# stereo_mix_back_digital.net
KiCad netlist of a schematic drawn in EAGLE
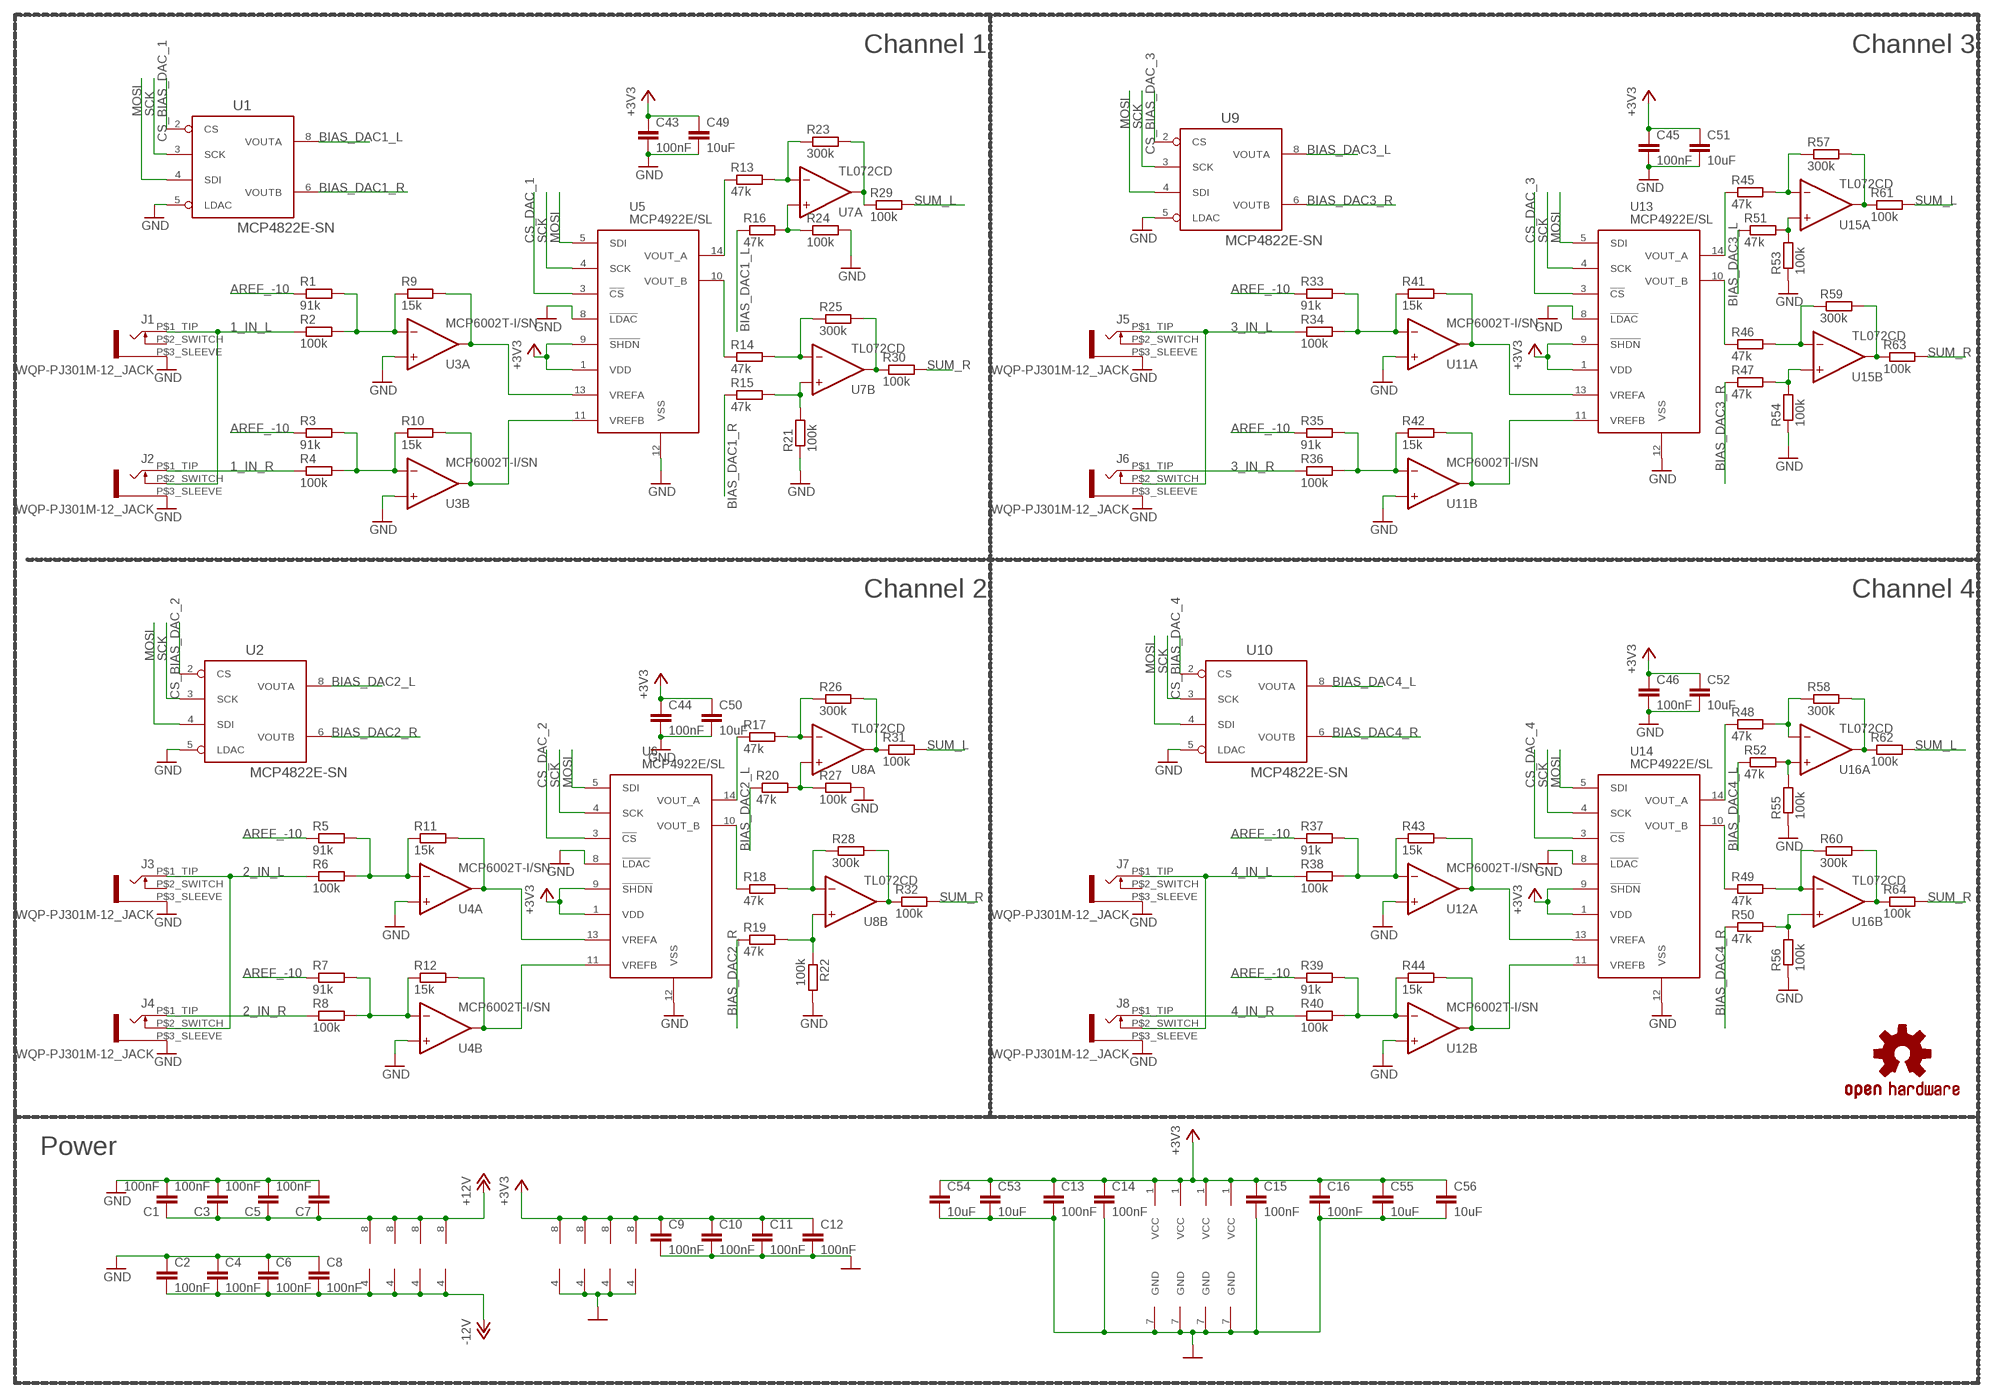
[diagram p0: schematic, sheet 1]
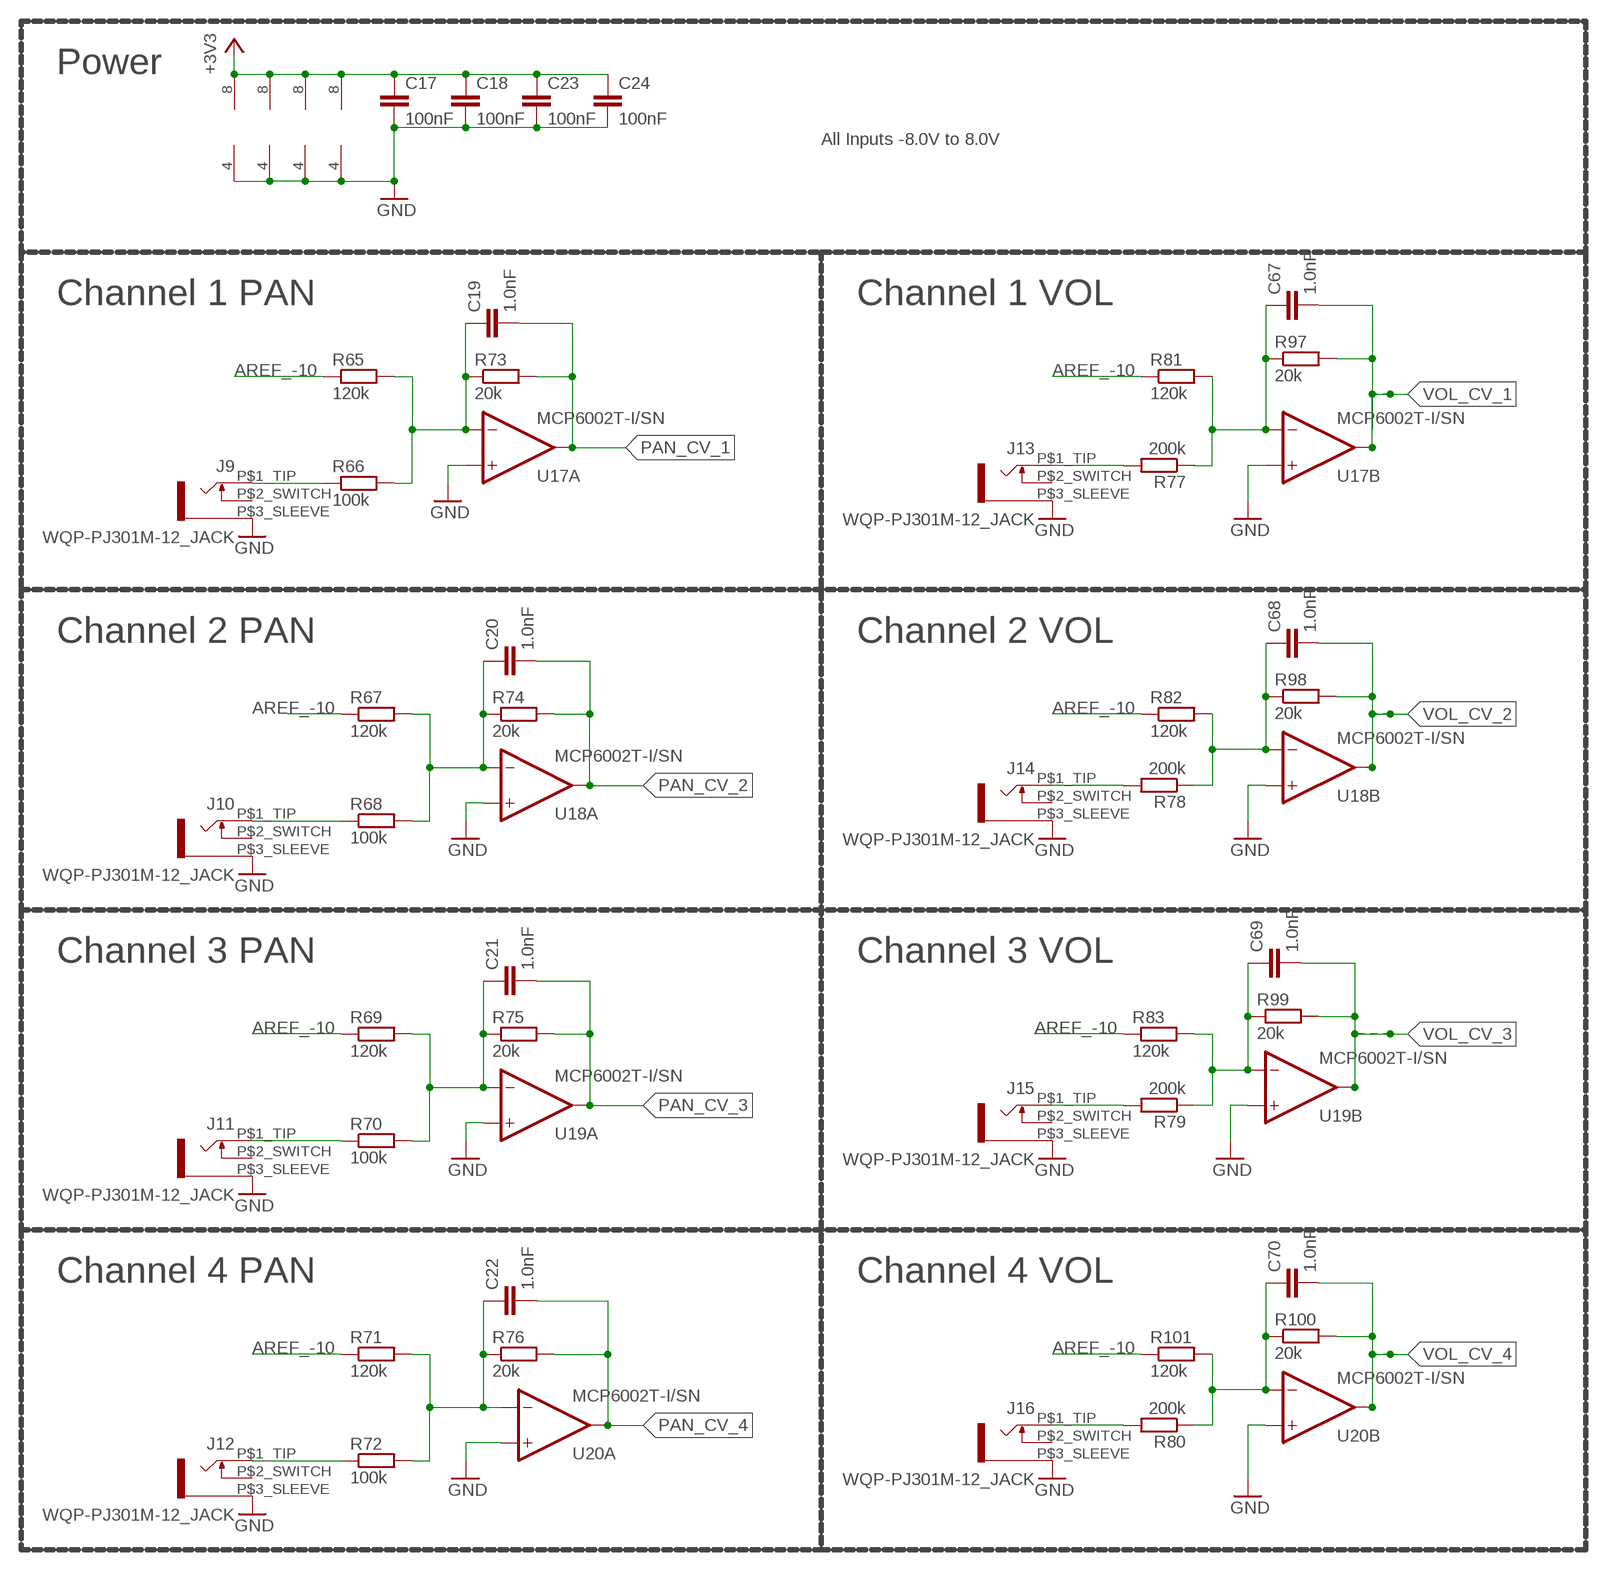
[diagram p1: schematic, sheet 2]
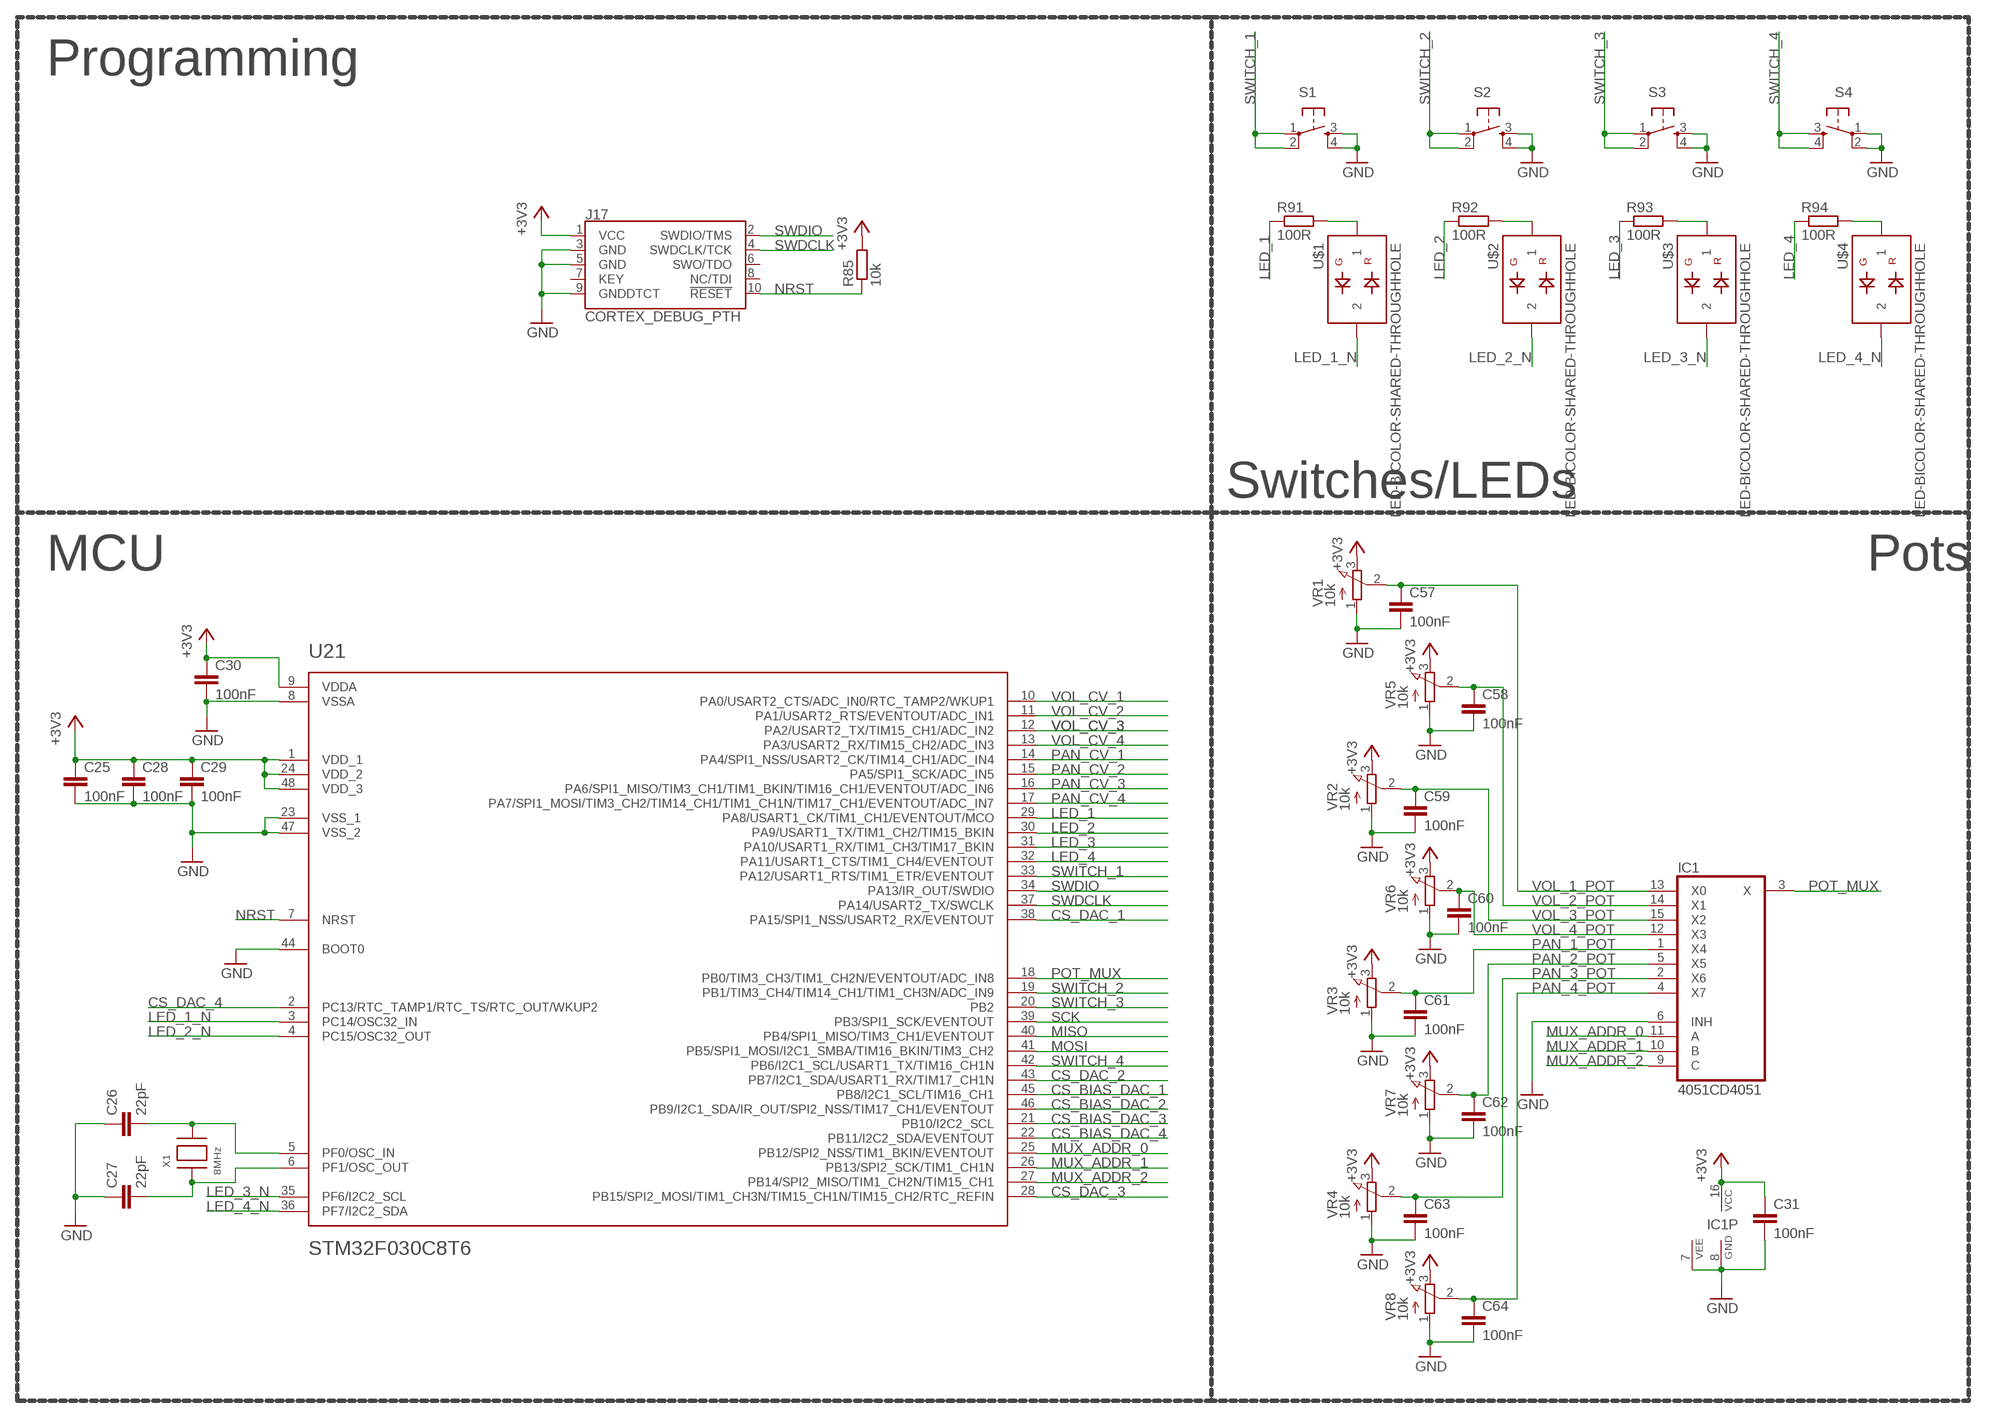
[diagram p2: schematic, sheet 3]
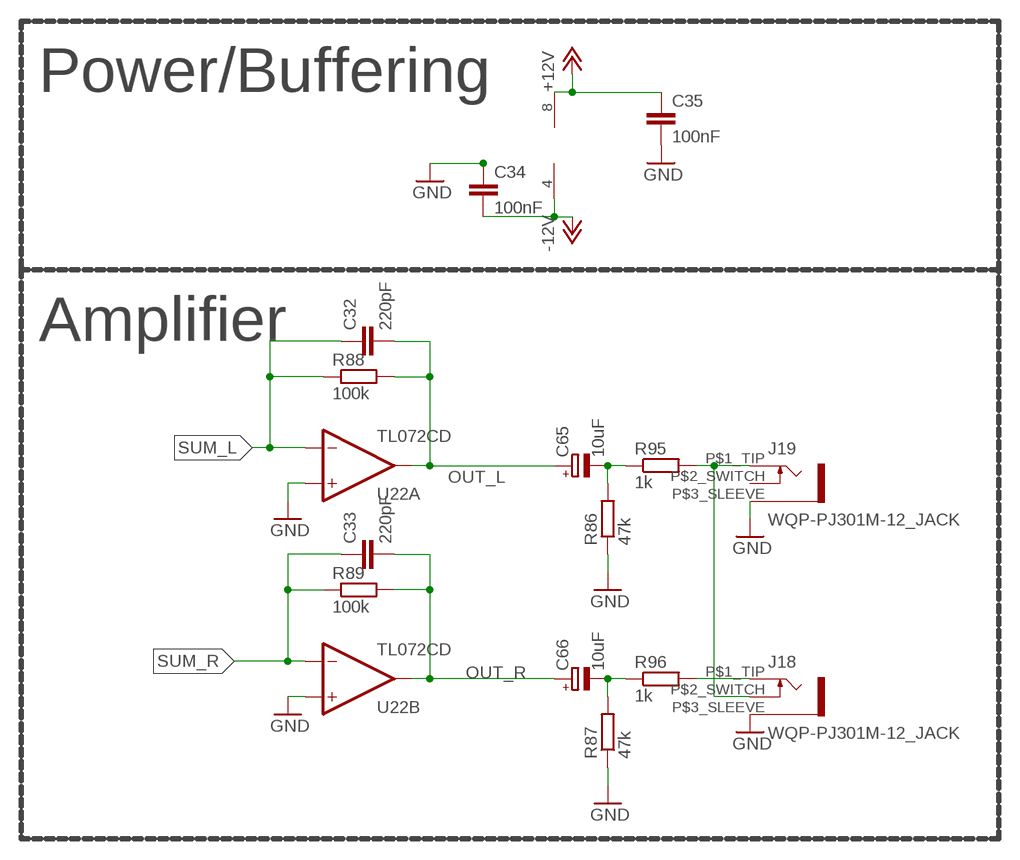
[diagram p3: schematic, sheet 4]
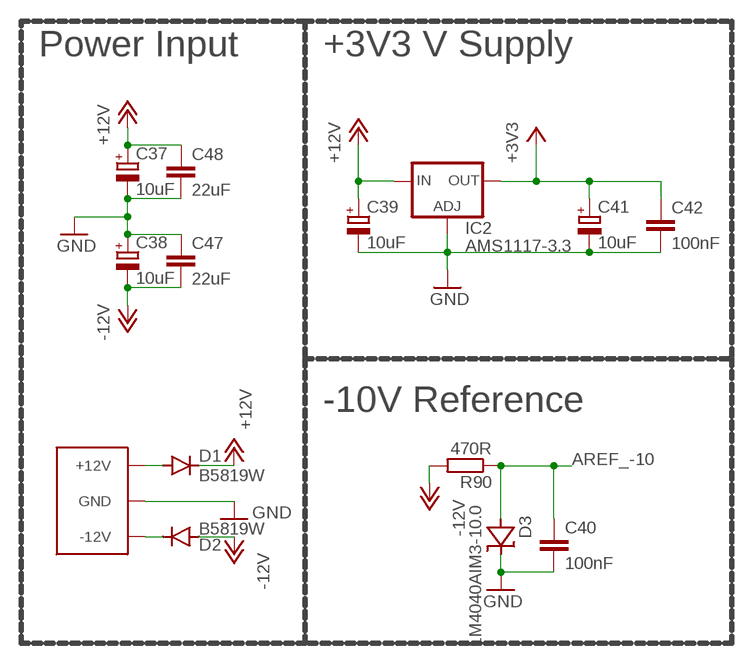
[diagram p4: schematic, sheet 5]

(export (version "E")
  (design (tool "Eeschema 10.0.6"))
  (components
    (comp (ref "C1")
      (value "100nF")
      (footprint "eagle-import:C0402")
      (libsource (lib "eagle-import") (part "C-EUC0402"))
    )
    (comp (ref "C2")
      (value "100nF")
      (footprint "eagle-import:C0402")
      (libsource (lib "eagle-import") (part "C-EUC0402"))
    )
    (comp (ref "C3")
      (value "100nF")
      (footprint "eagle-import:C0402")
      (libsource (lib "eagle-import") (part "C-EUC0402"))
    )
    (comp (ref "C4")
      (value "100nF")
      (footprint "eagle-import:C0402")
      (libsource (lib "eagle-import") (part "C-EUC0402"))
    )
    (comp (ref "C5")
      (value "100nF")
      (footprint "eagle-import:C0402")
      (libsource (lib "eagle-import") (part "C-EUC0402"))
    )
    (comp (ref "C6")
      (value "100nF")
      (footprint "eagle-import:C0402")
      (libsource (lib "eagle-import") (part "C-EUC0402"))
    )
    (comp (ref "C7")
      (value "100nF")
      (footprint "eagle-import:C0402")
      (libsource (lib "eagle-import") (part "C-EUC0402"))
    )
    (comp (ref "C8")
      (value "100nF")
      (footprint "eagle-import:C0402")
      (libsource (lib "eagle-import") (part "C-EUC0402"))
    )
    (comp (ref "C9")
      (value "100nF")
      (footprint "eagle-import:C0402")
      (libsource (lib "eagle-import") (part "C-EUC0402"))
    )
    (comp (ref "C10")
      (value "100nF")
      (footprint "eagle-import:C0402")
      (libsource (lib "eagle-import") (part "C-EUC0402"))
    )
    (comp (ref "C11")
      (value "100nF")
      (footprint "eagle-import:C0402")
      (libsource (lib "eagle-import") (part "C-EUC0402"))
    )
    (comp (ref "C12")
      (value "100nF")
      (footprint "eagle-import:C0402")
      (libsource (lib "eagle-import") (part "C-EUC0402"))
    )
    (comp (ref "C13")
      (value "100nF")
      (footprint "eagle-import:C0402")
      (libsource (lib "eagle-import") (part "C-EUC0402"))
    )
    (comp (ref "C14")
      (value "100nF")
      (footprint "eagle-import:C0402")
      (libsource (lib "eagle-import") (part "C-EUC0402"))
    )
    (comp (ref "C15")
      (value "100nF")
      (footprint "eagle-import:C0402")
      (libsource (lib "eagle-import") (part "C-EUC0402"))
    )
    (comp (ref "C16")
      (value "100nF")
      (footprint "eagle-import:C0402")
      (libsource (lib "eagle-import") (part "C-EUC0402"))
    )
    (comp (ref "C43")
      (value "100nF")
      (footprint "eagle-import:C0402")
      (libsource (lib "eagle-import") (part "C-EUC0402"))
    )
    (comp (ref "C44")
      (value "100nF")
      (footprint "eagle-import:C0402")
      (libsource (lib "eagle-import") (part "C-EUC0402"))
    )
    (comp (ref "C45")
      (value "100nF")
      (footprint "eagle-import:C0402")
      (libsource (lib "eagle-import") (part "jhbruhn-cr_C-EUC0402"))
    )
    (comp (ref "C46")
      (value "100nF")
      (footprint "eagle-import:C0402")
      (libsource (lib "eagle-import") (part "jhbruhn-cr_C-EUC0402"))
    )
    (comp (ref "C49")
      (value "10uF")
      (footprint "eagle-import:C0805")
      (libsource (lib "eagle-import") (part "C-EUC0805"))
    )
    (comp (ref "C50")
      (value "10uF")
      (footprint "eagle-import:C0805")
      (libsource (lib "eagle-import") (part "C-EUC0805"))
    )
    (comp (ref "C51")
      (value "10uF")
      (footprint "eagle-import:C0805")
      (libsource (lib "eagle-import") (part "C-EUC0805"))
    )
    (comp (ref "C52")
      (value "10uF")
      (footprint "eagle-import:C0805")
      (libsource (lib "eagle-import") (part "C-EUC0805"))
    )
    (comp (ref "C53")
      (value "10uF")
      (footprint "eagle-import:C0805")
      (libsource (lib "eagle-import") (part "C-EUC0805"))
    )
    (comp (ref "C54")
      (value "10uF")
      (footprint "eagle-import:C0805")
      (libsource (lib "eagle-import") (part "C-EUC0805"))
    )
    (comp (ref "C55")
      (value "10uF")
      (footprint "eagle-import:C0805")
      (libsource (lib "eagle-import") (part "C-EUC0805"))
    )
    (comp (ref "C56")
      (value "10uF")
      (footprint "eagle-import:C0805")
      (libsource (lib "eagle-import") (part "C-EUC0805"))
    )
    (comp (ref "J1")
      (value "WQP-PJ301M-12_JACK")
      (footprint "eagle-import:WQP-PJ301M-12_JACK")
      (libsource (lib "eagle-import") (part "WQP-PJ301M-12_JACK"))
    )
    (comp (ref "J2")
      (value "WQP-PJ301M-12_JACK")
      (footprint "eagle-import:WQP-PJ301M-12_JACK")
      (libsource (lib "eagle-import") (part "WQP-PJ301M-12_JACK"))
    )
    (comp (ref "J3")
      (value "WQP-PJ301M-12_JACK")
      (footprint "eagle-import:WQP-PJ301M-12_JACK")
      (libsource (lib "eagle-import") (part "WQP-PJ301M-12_JACK"))
    )
    (comp (ref "J4")
      (value "WQP-PJ301M-12_JACK")
      (footprint "eagle-import:WQP-PJ301M-12_JACK")
      (libsource (lib "eagle-import") (part "WQP-PJ301M-12_JACK"))
    )
    (comp (ref "J5")
      (value "WQP-PJ301M-12_JACK")
      (footprint "eagle-import:WQP-PJ301M-12_JACK")
      (libsource (lib "eagle-import") (part "WQP-PJ301M-12_JACK"))
    )
    (comp (ref "J6")
      (value "WQP-PJ301M-12_JACK")
      (footprint "eagle-import:WQP-PJ301M-12_JACK")
      (libsource (lib "eagle-import") (part "WQP-PJ301M-12_JACK"))
    )
    (comp (ref "J7")
      (value "WQP-PJ301M-12_JACK")
      (footprint "eagle-import:WQP-PJ301M-12_JACK")
      (libsource (lib "eagle-import") (part "WQP-PJ301M-12_JACK"))
    )
    (comp (ref "J8")
      (value "WQP-PJ301M-12_JACK")
      (footprint "eagle-import:WQP-PJ301M-12_JACK")
      (libsource (lib "eagle-import") (part "WQP-PJ301M-12_JACK"))
    )
    (comp (ref "LOGO1")
      (value "OSHW-LOGOS")
      (footprint "eagle-import:OSHW-LOGO-S")
      (libsource (lib "eagle-import") (part "OSHW-LOGOS"))
    )
    (comp (ref "R1")
      (value "91k")
      (footprint "eagle-import:R0402")
      (libsource (lib "eagle-import") (part "jhbruhn-cr_R-EU_R0402"))
    )
    (comp (ref "R2")
      (value "100k")
      (footprint "eagle-import:R0402")
      (libsource (lib "eagle-import") (part "jhbruhn-cr_R-EU_R0402"))
    )
    (comp (ref "R3")
      (value "91k")
      (footprint "eagle-import:R0402")
      (libsource (lib "eagle-import") (part "jhbruhn-cr_R-EU_R0402"))
    )
    (comp (ref "R4")
      (value "100k")
      (footprint "eagle-import:R0402")
      (libsource (lib "eagle-import") (part "jhbruhn-cr_R-EU_R0402"))
    )
    (comp (ref "R5")
      (value "91k")
      (footprint "eagle-import:R0402")
      (libsource (lib "eagle-import") (part "jhbruhn-cr_R-EU_R0402"))
    )
    (comp (ref "R6")
      (value "100k")
      (footprint "eagle-import:R0402")
      (libsource (lib "eagle-import") (part "jhbruhn-cr_R-EU_R0402"))
    )
    (comp (ref "R7")
      (value "91k")
      (footprint "eagle-import:R0402")
      (libsource (lib "eagle-import") (part "jhbruhn-cr_R-EU_R0402"))
    )
    (comp (ref "R8")
      (value "100k")
      (footprint "eagle-import:R0402")
      (libsource (lib "eagle-import") (part "jhbruhn-cr_R-EU_R0402"))
    )
    (comp (ref "R9")
      (value "15k")
      (footprint "eagle-import:R0402")
      (libsource (lib "eagle-import") (part "jhbruhn-cr_R-EU_R0402"))
    )
    (comp (ref "R10")
      (value "15k")
      (footprint "eagle-import:R0402")
      (libsource (lib "eagle-import") (part "jhbruhn-cr_R-EU_R0402"))
    )
    (comp (ref "R11")
      (value "15k")
      (footprint "eagle-import:R0402")
      (libsource (lib "eagle-import") (part "jhbruhn-cr_R-EU_R0402"))
    )
    (comp (ref "R12")
      (value "15k")
      (footprint "eagle-import:R0402")
      (libsource (lib "eagle-import") (part "jhbruhn-cr_R-EU_R0402"))
    )
    (comp (ref "R13")
      (value "47k")
      (footprint "eagle-import:R0402")
      (libsource (lib "eagle-import") (part "jhbruhn-cr_R-EU_R0402"))
    )
    (comp (ref "R14")
      (value "47k")
      (footprint "eagle-import:R0402")
      (libsource (lib "eagle-import") (part "jhbruhn-cr_R-EU_R0402"))
    )
    (comp (ref "R15")
      (value "47k")
      (footprint "eagle-import:R0402")
      (libsource (lib "eagle-import") (part "jhbruhn-cr_R-EU_R0402"))
    )
    (comp (ref "R16")
      (value "47k")
      (footprint "eagle-import:R0402")
      (libsource (lib "eagle-import") (part "jhbruhn-cr_R-EU_R0402"))
    )
    (comp (ref "R17")
      (value "47k")
      (footprint "eagle-import:R0402")
      (libsource (lib "eagle-import") (part "jhbruhn-cr_R-EU_R0402"))
    )
    (comp (ref "R18")
      (value "47k")
      (footprint "eagle-import:R0402")
      (libsource (lib "eagle-import") (part "jhbruhn-cr_R-EU_R0402"))
    )
    (comp (ref "R19")
      (value "47k")
      (footprint "eagle-import:R0402")
      (libsource (lib "eagle-import") (part "jhbruhn-cr_R-EU_R0402"))
    )
    (comp (ref "R20")
      (value "47k")
      (footprint "eagle-import:R0402")
      (libsource (lib "eagle-import") (part "jhbruhn-cr_R-EU_R0402"))
    )
    (comp (ref "R21")
      (value "100k")
      (footprint "eagle-import:R0402")
      (libsource (lib "eagle-import") (part "jhbruhn-cr_R-EU_R0402"))
    )
    (comp (ref "R22")
      (value "100k")
      (footprint "eagle-import:R0402")
      (libsource (lib "eagle-import") (part "jhbruhn-cr_R-EU_R0402"))
    )
    (comp (ref "R23")
      (value "300k")
      (footprint "eagle-import:R0402")
      (libsource (lib "eagle-import") (part "jhbruhn-cr_R-EU_R0402"))
    )
    (comp (ref "R24")
      (value "100k")
      (footprint "eagle-import:R0402")
      (libsource (lib "eagle-import") (part "jhbruhn-cr_R-EU_R0402"))
    )
    (comp (ref "R25")
      (value "300k")
      (footprint "eagle-import:R0402")
      (libsource (lib "eagle-import") (part "jhbruhn-cr_R-EU_R0402"))
    )
    (comp (ref "R26")
      (value "300k")
      (footprint "eagle-import:R0402")
      (libsource (lib "eagle-import") (part "jhbruhn-cr_R-EU_R0402"))
    )
    (comp (ref "R27")
      (value "100k")
      (footprint "eagle-import:R0402")
      (libsource (lib "eagle-import") (part "jhbruhn-cr_R-EU_R0402"))
    )
    (comp (ref "R28")
      (value "300k")
      (footprint "eagle-import:R0402")
      (libsource (lib "eagle-import") (part "jhbruhn-cr_R-EU_R0402"))
    )
    (comp (ref "R29")
      (value "100k")
      (footprint "eagle-import:R0402")
      (libsource (lib "eagle-import") (part "jhbruhn-cr_R-EU_R0402"))
    )
    (comp (ref "R30")
      (value "100k")
      (footprint "eagle-import:R0402")
      (libsource (lib "eagle-import") (part "jhbruhn-cr_R-EU_R0402"))
    )
    (comp (ref "R31")
      (value "100k")
      (footprint "eagle-import:R0402")
      (libsource (lib "eagle-import") (part "jhbruhn-cr_R-EU_R0402"))
    )
    (comp (ref "R32")
      (value "100k")
      (footprint "eagle-import:R0402")
      (libsource (lib "eagle-import") (part "jhbruhn-cr_R-EU_R0402"))
    )
    (comp (ref "R33")
      (value "91k")
      (footprint "eagle-import:R0402")
      (libsource (lib "eagle-import") (part "jhbruhn-cr_R-EU_R0402"))
    )
    (comp (ref "R34")
      (value "100k")
      (footprint "eagle-import:R0402")
      (libsource (lib "eagle-import") (part "jhbruhn-cr_R-EU_R0402"))
    )
    (comp (ref "R35")
      (value "91k")
      (footprint "eagle-import:R0402")
      (libsource (lib "eagle-import") (part "jhbruhn-cr_R-EU_R0402"))
    )
    (comp (ref "R36")
      (value "100k")
      (footprint "eagle-import:R0402")
      (libsource (lib "eagle-import") (part "jhbruhn-cr_R-EU_R0402"))
    )
    (comp (ref "R37")
      (value "91k")
      (footprint "eagle-import:R0402")
      (libsource (lib "eagle-import") (part "jhbruhn-cr_R-EU_R0402"))
    )
    (comp (ref "R38")
      (value "100k")
      (footprint "eagle-import:R0402")
      (libsource (lib "eagle-import") (part "jhbruhn-cr_R-EU_R0402"))
    )
    (comp (ref "R39")
      (value "91k")
      (footprint "eagle-import:R0402")
      (libsource (lib "eagle-import") (part "jhbruhn-cr_R-EU_R0402"))
    )
    (comp (ref "R40")
      (value "100k")
      (footprint "eagle-import:R0402")
      (libsource (lib "eagle-import") (part "jhbruhn-cr_R-EU_R0402"))
    )
    (comp (ref "R41")
      (value "15k")
      (footprint "eagle-import:R0402")
      (libsource (lib "eagle-import") (part "jhbruhn-cr_R-EU_R0402"))
    )
    (comp (ref "R42")
      (value "15k")
      (footprint "eagle-import:R0402")
      (libsource (lib "eagle-import") (part "jhbruhn-cr_R-EU_R0402"))
    )
    (comp (ref "R43")
      (value "15k")
      (footprint "eagle-import:R0402")
      (libsource (lib "eagle-import") (part "jhbruhn-cr_R-EU_R0402"))
    )
    (comp (ref "R44")
      (value "15k")
      (footprint "eagle-import:R0402")
      (libsource (lib "eagle-import") (part "jhbruhn-cr_R-EU_R0402"))
    )
    (comp (ref "R45")
      (value "47k")
      (footprint "eagle-import:R0402")
      (libsource (lib "eagle-import") (part "jhbruhn-cr_R-EU_R0402"))
    )
    (comp (ref "R46")
      (value "47k")
      (footprint "eagle-import:R0402")
      (libsource (lib "eagle-import") (part "jhbruhn-cr_R-EU_R0402"))
    )
    (comp (ref "R47")
      (value "47k")
      (footprint "eagle-import:R0402")
      (libsource (lib "eagle-import") (part "jhbruhn-cr_R-EU_R0402"))
    )
    (comp (ref "R48")
      (value "47k")
      (footprint "eagle-import:R0402")
      (libsource (lib "eagle-import") (part "jhbruhn-cr_R-EU_R0402"))
    )
    (comp (ref "R49")
      (value "47k")
      (footprint "eagle-import:R0402")
      (libsource (lib "eagle-import") (part "jhbruhn-cr_R-EU_R0402"))
    )
    (comp (ref "R50")
      (value "47k")
      (footprint "eagle-import:R0402")
      (libsource (lib "eagle-import") (part "jhbruhn-cr_R-EU_R0402"))
    )
    (comp (ref "R51")
      (value "47k")
      (footprint "eagle-import:R0402")
      (libsource (lib "eagle-import") (part "jhbruhn-cr_R-EU_R0402"))
    )
    (comp (ref "R52")
      (value "47k")
      (footprint "eagle-import:R0402")
      (libsource (lib "eagle-import") (part "jhbruhn-cr_R-EU_R0402"))
    )
    (comp (ref "R53")
      (value "100k")
      (footprint "eagle-import:R0402")
      (libsource (lib "eagle-import") (part "jhbruhn-cr_R-EU_R0402"))
    )
    (comp (ref "R54")
      (value "100k")
      (footprint "eagle-import:R0402")
      (libsource (lib "eagle-import") (part "jhbruhn-cr_R-EU_R0402"))
    )
    (comp (ref "R55")
      (value "100k")
      (footprint "eagle-import:R0402")
      (libsource (lib "eagle-import") (part "jhbruhn-cr_R-EU_R0402"))
    )
    (comp (ref "R56")
      (value "100k")
      (footprint "eagle-import:R0402")
      (libsource (lib "eagle-import") (part "jhbruhn-cr_R-EU_R0402"))
    )
    (comp (ref "R57")
      (value "300k")
      (footprint "eagle-import:R0402")
      (libsource (lib "eagle-import") (part "jhbruhn-cr_R-EU_R0402"))
    )
    (comp (ref "R58")
      (value "300k")
      (footprint "eagle-import:R0402")
      (libsource (lib "eagle-import") (part "jhbruhn-cr_R-EU_R0402"))
    )
    (comp (ref "R59")
      (value "300k")
      (footprint "eagle-import:R0402")
      (libsource (lib "eagle-import") (part "jhbruhn-cr_R-EU_R0402"))
    )
    (comp (ref "R60")
      (value "300k")
      (footprint "eagle-import:R0402")
      (libsource (lib "eagle-import") (part "jhbruhn-cr_R-EU_R0402"))
    )
    (comp (ref "R61")
      (value "100k")
      (footprint "eagle-import:R0402")
      (libsource (lib "eagle-import") (part "jhbruhn-cr_R-EU_R0402"))
    )
    (comp (ref "R62")
      (value "100k")
      (footprint "eagle-import:R0402")
      (libsource (lib "eagle-import") (part "jhbruhn-cr_R-EU_R0402"))
    )
    (comp (ref "R63")
      (value "100k")
      (footprint "eagle-import:R0402")
      (libsource (lib "eagle-import") (part "jhbruhn-cr_R-EU_R0402"))
    )
    (comp (ref "R64")
      (value "100k")
      (footprint "eagle-import:R0402")
      (libsource (lib "eagle-import") (part "jhbruhn-cr_R-EU_R0402"))
    )
    (comp (ref "U1")
      (value "MCP4822E-SN")
      (footprint "eagle-import:SOIC8")
      (libsource (lib "eagle-import") (part "MCP482E-SN2"))
    )
    (comp (ref "U2")
      (value "MCP4822E-SN")
      (footprint "eagle-import:SOIC8")
      (libsource (lib "eagle-import") (part "MCP482E-SN2"))
    )
    (comp (ref "U3")
      (value "MCP6002T-I/SN")
      (footprint "eagle-import:SOIC8")
      (libsource (lib "eagle-import") (part "MCP6002T-I/SN"))
    )
    (comp (ref "U4")
      (value "MCP6002T-I/SN")
      (footprint "eagle-import:SOIC8")
      (libsource (lib "eagle-import") (part "MCP6002T-I/SN"))
    )
    (comp (ref "U5")
      (value "MCP4922E/SL")
      (footprint "eagle-import:SO-14")
      (libsource (lib "eagle-import") (part "MCP492E/SL2"))
    )
    (comp (ref "U6")
      (value "MCP4922E/SL")
      (footprint "eagle-import:SO-14")
      (libsource (lib "eagle-import") (part "MCP492E/SL2"))
    )
    (comp (ref "U7")
      (value "TL072CD")
      (footprint "eagle-import:SOIC8")
      (libsource (lib "eagle-import") (part "TL072DC"))
    )
    (comp (ref "U8")
      (value "TL072CD")
      (footprint "eagle-import:SOIC8")
      (libsource (lib "eagle-import") (part "TL072DC"))
    )
    (comp (ref "U9")
      (value "MCP4822E-SN")
      (footprint "eagle-import:SOIC8")
      (libsource (lib "eagle-import") (part "MCP482E-SN2"))
    )
    (comp (ref "U10")
      (value "MCP4822E-SN")
      (footprint "eagle-import:SOIC8")
      (libsource (lib "eagle-import") (part "MCP482E-SN2"))
    )
    (comp (ref "U11")
      (value "MCP6002T-I/SN")
      (footprint "eagle-import:SOIC8")
      (libsource (lib "eagle-import") (part "MCP6002T-I/SN"))
    )
    (comp (ref "U12")
      (value "MCP6002T-I/SN")
      (footprint "eagle-import:SOIC8")
      (libsource (lib "eagle-import") (part "MCP6002T-I/SN"))
    )
    (comp (ref "U13")
      (value "MCP4922E/SL")
      (footprint "eagle-import:SO-14")
      (libsource (lib "eagle-import") (part "MCP492E/SL2"))
    )
    (comp (ref "U14")
      (value "MCP4922E/SL")
      (footprint "eagle-import:SO-14")
      (libsource (lib "eagle-import") (part "MCP492E/SL2"))
    )
    (comp (ref "U15")
      (value "TL072CD")
      (footprint "eagle-import:SOIC8")
      (libsource (lib "eagle-import") (part "TL072DC"))
    )
    (comp (ref "U16")
      (value "TL072CD")
      (footprint "eagle-import:SOIC8")
      (libsource (lib "eagle-import") (part "TL072DC"))
    )
    (comp (ref "C25")
      (value "100nF")
      (footprint "eagle-import:C0402")
      (libsource (lib "eagle-import") (part "C-EUC0402"))
    )
    (comp (ref "C26")
      (value "22pF")
      (footprint "eagle-import:C0402")
      (libsource (lib "eagle-import") (part "C-EUC0402"))
    )
    (comp (ref "C27")
      (value "22pF")
      (footprint "eagle-import:C0402")
      (libsource (lib "eagle-import") (part "C-EUC0402"))
    )
    (comp (ref "C28")
      (value "100nF")
      (footprint "eagle-import:C0402")
      (libsource (lib "eagle-import") (part "C-EUC0402"))
    )
    (comp (ref "C29")
      (value "100nF")
      (footprint "eagle-import:C0402")
      (libsource (lib "eagle-import") (part "C-EUC0402"))
    )
    (comp (ref "C30")
      (value "100nF")
      (footprint "eagle-import:C0402")
      (libsource (lib "eagle-import") (part "C-EUC0402"))
    )
    (comp (ref "C31")
      (value "100nF")
      (footprint "eagle-import:C0402")
      (libsource (lib "eagle-import") (part "C-EUC0402"))
    )
    (comp (ref "C57")
      (value "100nF")
      (footprint "eagle-import:C0402")
      (libsource (lib "eagle-import") (part "C-EUC0402"))
    )
    (comp (ref "C58")
      (value "100nF")
      (footprint "eagle-import:C0402")
      (libsource (lib "eagle-import") (part "C-EUC0402"))
    )
    (comp (ref "C59")
      (value "100nF")
      (footprint "eagle-import:C0402")
      (libsource (lib "eagle-import") (part "C-EUC0402"))
    )
    (comp (ref "C60")
      (value "100nF")
      (footprint "eagle-import:C0402")
      (libsource (lib "eagle-import") (part "C-EUC0402"))
    )
    (comp (ref "C61")
      (value "100nF")
      (footprint "eagle-import:C0402")
      (libsource (lib "eagle-import") (part "C-EUC0402"))
    )
    (comp (ref "C62")
      (value "100nF")
      (footprint "eagle-import:C0402")
      (libsource (lib "eagle-import") (part "C-EUC0402"))
    )
    (comp (ref "C63")
      (value "100nF")
      (footprint "eagle-import:C0402")
      (libsource (lib "eagle-import") (part "C-EUC0402"))
    )
    (comp (ref "C64")
      (value "100nF")
      (footprint "eagle-import:C0402")
      (libsource (lib "eagle-import") (part "C-EUC0402"))
    )
    (comp (ref "IC1")
      (value "4051CD4051")
      (footprint "eagle-import:SOIC16N")
      (libsource (lib "eagle-import") (part "4051CD4051"))
    )
    (comp (ref "J17")
      (value "CORTEX_DEBUG_PTH")
      (footprint "eagle-import:2X5-PTH-1.27MM")
      (libsource (lib "eagle-import") (part "CORTEX_DEBUG_PTH"))
    )
    (comp (ref "R85")
      (value "10k")
      (footprint "eagle-import:R0402")
      (libsource (lib "eagle-import") (part "jhbruhn-cr_R-EU_R0402"))
    )
    (comp (ref "R91")
      (value "100R")
      (footprint "eagle-import:R0402")
      (libsource (lib "eagle-import") (part "R-EU_R0402"))
    )
    (comp (ref "R92")
      (value "100R")
      (footprint "eagle-import:R0402")
      (libsource (lib "eagle-import") (part "R-EU_R0402"))
    )
    (comp (ref "R93")
      (value "100R")
      (footprint "eagle-import:R0402")
      (libsource (lib "eagle-import") (part "R-EU_R0402"))
    )
    (comp (ref "R94")
      (value "100R")
      (footprint "eagle-import:R0402")
      (libsource (lib "eagle-import") (part "R-EU_R0402"))
    )
    (comp (ref "S1")
      (value "TAC_SWITCHPTH")
      (footprint "eagle-import:TACTILE-PTH")
      (libsource (lib "eagle-import") (part "TAC_SWITCHPTH"))
    )
    (comp (ref "S2")
      (value "TAC_SWITCHPTH")
      (footprint "eagle-import:TACTILE-PTH")
      (libsource (lib "eagle-import") (part "TAC_SWITCHPTH"))
    )
    (comp (ref "S3")
      (value "TAC_SWITCHPTH")
      (footprint "eagle-import:TACTILE-PTH")
      (libsource (lib "eagle-import") (part "TAC_SWITCHPTH"))
    )
    (comp (ref "S4")
      (value "TAC_SWITCHPTH")
      (footprint "eagle-import:TACTILE-PTH")
      (libsource (lib "eagle-import") (part "TAC_SWITCHPTH"))
    )
    (comp (ref "U$1")
      (value "LED-BICOLOR-SHARED-THROUGHHOLE")
      (footprint "eagle-import:LED3MM")
      (libsource (lib "eagle-import") (part "LED-BICOLOR-SHARED-THROUGHHOLE"))
    )
    (comp (ref "U$2")
      (value "LED-BICOLOR-SHARED-THROUGHHOLE")
      (footprint "eagle-import:LED3MM")
      (libsource (lib "eagle-import") (part "LED-BICOLOR-SHARED-THROUGHHOLE"))
    )
    (comp (ref "U$3")
      (value "LED-BICOLOR-SHARED-THROUGHHOLE")
      (footprint "eagle-import:LED3MM")
      (libsource (lib "eagle-import") (part "LED-BICOLOR-SHARED-THROUGHHOLE"))
    )
    (comp (ref "U$4")
      (value "LED-BICOLOR-SHARED-THROUGHHOLE")
      (footprint "eagle-import:LED3MM")
      (libsource (lib "eagle-import") (part "LED-BICOLOR-SHARED-THROUGHHOLE"))
    )
    (comp (ref "U21")
      (value "STM32F030C8T6")
      (footprint "eagle-import:LQFP48")
      (libsource (lib "eagle-import") (part "STM32F030C8T6"))
    )
    (comp (ref "VR1")
      (value "10k")
      (footprint "eagle-import:9MM_SNAP-IN_POT")
      (libsource (lib "eagle-import") (part "9MM_SNAP-IN_POT_"))
    )
    (comp (ref "VR2")
      (value "10k")
      (footprint "eagle-import:9MM_SNAP-IN_POT")
      (libsource (lib "eagle-import") (part "9MM_SNAP-IN_POT_"))
    )
    (comp (ref "VR3")
      (value "10k")
      (footprint "eagle-import:9MM_SNAP-IN_POT")
      (libsource (lib "eagle-import") (part "9MM_SNAP-IN_POT_"))
    )
    (comp (ref "VR4")
      (value "10k")
      (footprint "eagle-import:9MM_SNAP-IN_POT")
      (libsource (lib "eagle-import") (part "9MM_SNAP-IN_POT_"))
    )
    (comp (ref "VR5")
      (value "10k")
      (footprint "eagle-import:9MM_SNAP-IN_POT")
      (libsource (lib "eagle-import") (part "9MM_SNAP-IN_POT_"))
    )
    (comp (ref "VR6")
      (value "10k")
      (footprint "eagle-import:9MM_SNAP-IN_POT")
      (libsource (lib "eagle-import") (part "9MM_SNAP-IN_POT_"))
    )
    (comp (ref "VR7")
      (value "10k")
      (footprint "eagle-import:9MM_SNAP-IN_POT")
      (libsource (lib "eagle-import") (part "9MM_SNAP-IN_POT_"))
    )
    (comp (ref "VR8")
      (value "10k")
      (footprint "eagle-import:9MM_SNAP-IN_POT")
      (libsource (lib "eagle-import") (part "9MM_SNAP-IN_POT_"))
    )
    (comp (ref "X1")
      (value "8MHz")
      (footprint "eagle-import:NX5032")
      (libsource (lib "eagle-import") (part "XTALNX5032"))
    )
    (comp (ref "C17")
      (value "100nF")
      (footprint "eagle-import:C0402")
      (libsource (lib "eagle-import") (part "C-EUC0402"))
    )
    (comp (ref "C18")
      (value "100nF")
      (footprint "eagle-import:C0402")
      (libsource (lib "eagle-import") (part "C-EUC0402"))
    )
    (comp (ref "C19")
      (value "1.0nF")
      (footprint "eagle-import:C0402")
      (libsource (lib "eagle-import") (part "C-EUC0402"))
    )
    (comp (ref "C20")
      (value "1.0nF")
      (footprint "eagle-import:C0402")
      (libsource (lib "eagle-import") (part "C-EUC0402"))
    )
    (comp (ref "C21")
      (value "1.0nF")
      (footprint "eagle-import:C0402")
      (libsource (lib "eagle-import") (part "C-EUC0402"))
    )
    (comp (ref "C22")
      (value "1.0nF")
      (footprint "eagle-import:C0402")
      (libsource (lib "eagle-import") (part "C-EUC0402"))
    )
    (comp (ref "C23")
      (value "100nF")
      (footprint "eagle-import:C0402")
      (libsource (lib "eagle-import") (part "C-EUC0402"))
    )
    (comp (ref "C24")
      (value "100nF")
      (footprint "eagle-import:C0402")
      (libsource (lib "eagle-import") (part "C-EUC0402"))
    )
    (comp (ref "C67")
      (value "1.0nF")
      (footprint "eagle-import:C0402")
      (libsource (lib "eagle-import") (part "C-EUC0402"))
    )
    (comp (ref "C68")
      (value "1.0nF")
      (footprint "eagle-import:C0402")
      (libsource (lib "eagle-import") (part "C-EUC0402"))
    )
    (comp (ref "C69")
      (value "1.0nF")
      (footprint "eagle-import:C0402")
      (libsource (lib "eagle-import") (part "C-EUC0402"))
    )
    (comp (ref "C70")
      (value "1.0nF")
      (footprint "eagle-import:C0402")
      (libsource (lib "eagle-import") (part "C-EUC0402"))
    )
    (comp (ref "J9")
      (value "WQP-PJ301M-12_JACK")
      (footprint "eagle-import:WQP-PJ301M-12_JACK")
      (libsource (lib "eagle-import") (part "WQP-PJ301M-12_JACK"))
    )
    (comp (ref "J10")
      (value "WQP-PJ301M-12_JACK")
      (footprint "eagle-import:WQP-PJ301M-12_JACK")
      (libsource (lib "eagle-import") (part "WQP-PJ301M-12_JACK"))
    )
    (comp (ref "J11")
      (value "WQP-PJ301M-12_JACK")
      (footprint "eagle-import:WQP-PJ301M-12_JACK")
      (libsource (lib "eagle-import") (part "WQP-PJ301M-12_JACK"))
    )
    (comp (ref "J12")
      (value "WQP-PJ301M-12_JACK")
      (footprint "eagle-import:WQP-PJ301M-12_JACK")
      (libsource (lib "eagle-import") (part "WQP-PJ301M-12_JACK"))
    )
    (comp (ref "J13")
      (value "WQP-PJ301M-12_JACK")
      (footprint "eagle-import:WQP-PJ301M-12_JACK")
      (libsource (lib "eagle-import") (part "WQP-PJ301M-12_JACK"))
    )
    (comp (ref "J14")
      (value "WQP-PJ301M-12_JACK")
      (footprint "eagle-import:WQP-PJ301M-12_JACK")
      (libsource (lib "eagle-import") (part "WQP-PJ301M-12_JACK"))
    )
    (comp (ref "J15")
      (value "WQP-PJ301M-12_JACK")
      (footprint "eagle-import:WQP-PJ301M-12_JACK")
      (libsource (lib "eagle-import") (part "WQP-PJ301M-12_JACK"))
    )
    (comp (ref "J16")
      (value "WQP-PJ301M-12_JACK")
      (footprint "eagle-import:WQP-PJ301M-12_JACK")
      (libsource (lib "eagle-import") (part "WQP-PJ301M-12_JACK"))
    )
    (comp (ref "R65")
      (value "120k")
      (footprint "eagle-import:R0402")
      (libsource (lib "eagle-import") (part "jhbruhn-cr_R-EU_R0402"))
    )
    (comp (ref "R66")
      (value "100k")
      (footprint "eagle-import:R0402")
      (libsource (lib "eagle-import") (part "jhbruhn-cr_R-EU_R0402"))
    )
    (comp (ref "R67")
      (value "120k")
      (footprint "eagle-import:R0402")
      (libsource (lib "eagle-import") (part "jhbruhn-cr_R-EU_R0402"))
    )
    (comp (ref "R68")
      (value "100k")
      (footprint "eagle-import:R0402")
      (libsource (lib "eagle-import") (part "jhbruhn-cr_R-EU_R0402"))
    )
    (comp (ref "R69")
      (value "120k")
      (footprint "eagle-import:R0402")
      (libsource (lib "eagle-import") (part "jhbruhn-cr_R-EU_R0402"))
    )
    (comp (ref "R70")
      (value "100k")
      (footprint "eagle-import:R0402")
      (libsource (lib "eagle-import") (part "jhbruhn-cr_R-EU_R0402"))
    )
    (comp (ref "R71")
      (value "120k")
      (footprint "eagle-import:R0402")
      (libsource (lib "eagle-import") (part "jhbruhn-cr_R-EU_R0402"))
    )
    (comp (ref "R72")
      (value "100k")
      (footprint "eagle-import:R0402")
      (libsource (lib "eagle-import") (part "jhbruhn-cr_R-EU_R0402"))
    )
    (comp (ref "R73")
      (value "20k")
      (footprint "eagle-import:R0402")
      (libsource (lib "eagle-import") (part "jhbruhn-cr_R-EU_R0402"))
    )
    (comp (ref "R74")
      (value "20k")
      (footprint "eagle-import:R0402")
      (libsource (lib "eagle-import") (part "jhbruhn-cr_R-EU_R0402"))
    )
    (comp (ref "R75")
      (value "20k")
      (footprint "eagle-import:R0402")
      (libsource (lib "eagle-import") (part "jhbruhn-cr_R-EU_R0402"))
    )
    (comp (ref "R76")
      (value "20k")
      (footprint "eagle-import:R0402")
      (libsource (lib "eagle-import") (part "jhbruhn-cr_R-EU_R0402"))
    )
    (comp (ref "R77")
      (value "200k")
      (footprint "eagle-import:R0402")
      (libsource (lib "eagle-import") (part "jhbruhn-cr_R-EU_R0402"))
    )
    (comp (ref "R78")
      (value "200k")
      (footprint "eagle-import:R0402")
      (libsource (lib "eagle-import") (part "jhbruhn-cr_R-EU_R0402"))
    )
    (comp (ref "R79")
      (value "200k")
      (footprint "eagle-import:R0402")
      (libsource (lib "eagle-import") (part "jhbruhn-cr_R-EU_R0402"))
    )
    (comp (ref "R80")
      (value "200k")
      (footprint "eagle-import:R0402")
      (libsource (lib "eagle-import") (part "jhbruhn-cr_R-EU_R0402"))
    )
    (comp (ref "R81")
      (value "120k")
      (footprint "eagle-import:R0402")
      (libsource (lib "eagle-import") (part "jhbruhn-cr_R-EU_R0402"))
    )
    (comp (ref "R82")
      (value "120k")
      (footprint "eagle-import:R0402")
      (libsource (lib "eagle-import") (part "jhbruhn-cr_R-EU_R0402"))
    )
    (comp (ref "R83")
      (value "120k")
      (footprint "eagle-import:R0402")
      (libsource (lib "eagle-import") (part "jhbruhn-cr_R-EU_R0402"))
    )
    (comp (ref "R97")
      (value "20k")
      (footprint "eagle-import:R0402")
      (libsource (lib "eagle-import") (part "jhbruhn-cr_R-EU_R0402"))
    )
    (comp (ref "R98")
      (value "20k")
      (footprint "eagle-import:R0402")
      (libsource (lib "eagle-import") (part "jhbruhn-cr_R-EU_R0402"))
    )
    (comp (ref "R99")
      (value "20k")
      (footprint "eagle-import:R0402")
      (libsource (lib "eagle-import") (part "jhbruhn-cr_R-EU_R0402"))
    )
    (comp (ref "R100")
      (value "20k")
      (footprint "eagle-import:R0402")
      (libsource (lib "eagle-import") (part "jhbruhn-cr_R-EU_R0402"))
    )
    (comp (ref "R101")
      (value "120k")
      (footprint "eagle-import:R0402")
      (libsource (lib "eagle-import") (part "jhbruhn-cr_R-EU_R0402"))
    )
    (comp (ref "U17")
      (value "MCP6002T-I/SN")
      (footprint "eagle-import:SOIC8")
      (libsource (lib "eagle-import") (part "MCP6002T-I/SN"))
    )
    (comp (ref "U18")
      (value "MCP6002T-I/SN")
      (footprint "eagle-import:SOIC8")
      (libsource (lib "eagle-import") (part "MCP6002T-I/SN"))
    )
    (comp (ref "U19")
      (value "MCP6002T-I/SN")
      (footprint "eagle-import:SOIC8")
      (libsource (lib "eagle-import") (part "MCP6002T-I/SN"))
    )
    (comp (ref "U20")
      (value "MCP6002T-I/SN")
      (footprint "eagle-import:SOIC8")
      (libsource (lib "eagle-import") (part "MCP6002T-I/SN"))
    )
    (comp (ref "C36")
      (value "EURO_POWER_LOCKFAT-LOCK")
      (footprint "eagle-import:EURO_PWR_HEADER_LOCK")
      (libsource (lib "eagle-import") (part "EURO_POWER_LOCKFAT-LOCK"))
    )
    (comp (ref "C37")
      (value "10uF")
      (footprint "eagle-import:CASE-A_3216")
      (libsource (lib "eagle-import") (part "CPOL-EUA/3216-18R"))
    )
    (comp (ref "C38")
      (value "10uF")
      (footprint "eagle-import:CASE-A_3216")
      (libsource (lib "eagle-import") (part "CPOL-EUA/3216-18R"))
    )
    (comp (ref "C39")
      (value "10uF")
      (footprint "eagle-import:CASE-A_3216")
      (libsource (lib "eagle-import") (part "CPOL-EUA/3216-18R"))
    )
    (comp (ref "C40")
      (value "100nF")
      (footprint "eagle-import:C0402")
      (libsource (lib "eagle-import") (part "C-EUC0402"))
    )
    (comp (ref "C41")
      (value "10uF")
      (footprint "eagle-import:CASE-A_3216")
      (libsource (lib "eagle-import") (part "CPOL-EUA/3216-18R"))
    )
    (comp (ref "C42")
      (value "100nF")
      (footprint "eagle-import:C0402")
      (libsource (lib "eagle-import") (part "C-EUC0402"))
    )
    (comp (ref "C47")
      (value "22uF")
      (footprint "eagle-import:C0805")
      (libsource (lib "eagle-import") (part "C-EUC0805"))
    )
    (comp (ref "C48")
      (value "22uF")
      (footprint "eagle-import:C0805")
      (libsource (lib "eagle-import") (part "C-EUC0805"))
    )
    (comp (ref "D1")
      (value "B5819W")
      (footprint "eagle-import:SOD123")
      (libsource (lib "eagle-import") (part "DIODE-SOD123"))
    )
    (comp (ref "D2")
      (value "B5819W")
      (footprint "eagle-import:SOD123")
      (libsource (lib "eagle-import") (part "DIODE-SOD123"))
    )
    (comp (ref "D3")
      (value "LM4040AIM3-10.0")
      (footprint "eagle-import:SOT23")
      (libsource (lib "eagle-import") (part "LM4040-10.0AIM3"))
    )
    (comp (ref "IC2")
      (value "AMS1117-3.3")
      (footprint "eagle-import:SOT223")
      (libsource (lib "eagle-import") (part "AMS1117-3.3"))
    )
    (comp (ref "R90")
      (value "470R")
      (footprint "eagle-import:R0402")
      (libsource (lib "eagle-import") (part "jhbruhn-cr_R-EU_R0402"))
    )
    (comp (ref "C32")
      (value "220pF")
      (footprint "eagle-import:C0402")
      (libsource (lib "eagle-import") (part "C-EUC0402"))
    )
    (comp (ref "C33")
      (value "220pF")
      (footprint "eagle-import:C0402")
      (libsource (lib "eagle-import") (part "C-EUC0402"))
    )
    (comp (ref "C34")
      (value "100nF")
      (footprint "eagle-import:C0402")
      (libsource (lib "eagle-import") (part "C-EUC0402"))
    )
    (comp (ref "C35")
      (value "100nF")
      (footprint "eagle-import:C0402")
      (libsource (lib "eagle-import") (part "C-EUC0402"))
    )
    (comp (ref "C65")
      (value "10uF")
      (footprint "eagle-import:CASE-A_3216")
      (libsource (lib "eagle-import") (part "CPOL-EUA/3216-18R"))
    )
    (comp (ref "C66")
      (value "10uF")
      (footprint "eagle-import:CASE-A_3216")
      (libsource (lib "eagle-import") (part "CPOL-EUA/3216-18R"))
    )
    (comp (ref "J18")
      (value "WQP-PJ301M-12_JACK")
      (footprint "eagle-import:WQP-PJ301M-12_JACK")
      (libsource (lib "eagle-import") (part "WQP-PJ301M-12_JACK"))
    )
    (comp (ref "J19")
      (value "WQP-PJ301M-12_JACK")
      (footprint "eagle-import:WQP-PJ301M-12_JACK")
      (libsource (lib "eagle-import") (part "WQP-PJ301M-12_JACK"))
    )
    (comp (ref "R86")
      (value "47k")
      (footprint "eagle-import:R0402")
      (libsource (lib "eagle-import") (part "R-EU_R0402"))
    )
    (comp (ref "R87")
      (value "47k")
      (footprint "eagle-import:R0402")
      (libsource (lib "eagle-import") (part "R-EU_R0402"))
    )
    (comp (ref "R88")
      (value "100k")
      (footprint "eagle-import:R0402")
      (libsource (lib "eagle-import") (part "jhbruhn-cr_R-EU_R0402"))
    )
    (comp (ref "R89")
      (value "100k")
      (footprint "eagle-import:R0402")
      (libsource (lib "eagle-import") (part "jhbruhn-cr_R-EU_R0402"))
    )
    (comp (ref "R95")
      (value "1k")
      (footprint "eagle-import:R0402")
      (libsource (lib "eagle-import") (part "R-EU_R0402"))
    )
    (comp (ref "R96")
      (value "1k")
      (footprint "eagle-import:R0402")
      (libsource (lib "eagle-import") (part "R-EU_R0402"))
    )
    (comp (ref "U22")
      (value "TL072CD")
      (footprint "eagle-import:SOIC8")
      (libsource (lib "eagle-import") (part "TL072DC"))
    )
  )
  (nets
    (net (code "1") (name "+3V3") (class "Default")
      (node (ref "C10") (pin "1") (pinfunction "1_1") (pintype "passive"))
      (node (ref "C11") (pin "1") (pinfunction "1_1") (pintype "passive"))
      (node (ref "C12") (pin "1") (pinfunction "1_1") (pintype "passive"))
      (node (ref "C13") (pin "1") (pinfunction "1_1") (pintype "passive"))
      (node (ref "C14") (pin "1") (pinfunction "1_1") (pintype "passive"))
      (node (ref "C15") (pin "1") (pinfunction "1_1") (pintype "passive"))
      (node (ref "C16") (pin "1") (pinfunction "1_1") (pintype "passive"))
      (node (ref "C17") (pin "1") (pinfunction "1_1") (pintype "passive"))
      (node (ref "C18") (pin "1") (pinfunction "1_1") (pintype "passive"))
      (node (ref "C23") (pin "1") (pinfunction "1_1") (pintype "passive"))
      (node (ref "C24") (pin "1") (pinfunction "1_1") (pintype "passive"))
      (node (ref "C25") (pin "1") (pinfunction "1_1") (pintype "passive"))
      (node (ref "C28") (pin "1") (pinfunction "1_1") (pintype "passive"))
      (node (ref "C29") (pin "1") (pinfunction "1_1") (pintype "passive"))
      (node (ref "C30") (pin "1") (pinfunction "1_1") (pintype "passive"))
      (node (ref "C31") (pin "1") (pinfunction "1_1") (pintype "passive"))
      (node (ref "C41") (pin "+") (pinfunction "+_+") (pintype "passive"))
      (node (ref "C42") (pin "1") (pinfunction "1_1") (pintype "passive"))
      (node (ref "C43") (pin "1") (pinfunction "1_1") (pintype "passive"))
      (node (ref "C44") (pin "1") (pinfunction "1_1") (pintype "passive"))
      (node (ref "C45") (pin "1") (pinfunction "1_1") (pintype "passive"))
      (node (ref "C46") (pin "1") (pinfunction "1_1") (pintype "passive"))
      (node (ref "C49") (pin "1") (pinfunction "1_1") (pintype "passive"))
      (node (ref "C50") (pin "1") (pinfunction "1_1") (pintype "passive"))
      (node (ref "C51") (pin "1") (pinfunction "1_1") (pintype "passive"))
      (node (ref "C52") (pin "1") (pinfunction "1_1") (pintype "passive"))
      (node (ref "C53") (pin "1") (pinfunction "1_1") (pintype "passive"))
      (node (ref "C54") (pin "1") (pinfunction "1_1") (pintype "passive"))
      (node (ref "C55") (pin "1") (pinfunction "1_1") (pintype "passive"))
      (node (ref "C56") (pin "1") (pinfunction "1_1") (pintype "passive"))
      (node (ref "C9") (pin "1") (pinfunction "1_1") (pintype "passive"))
      (node (ref "IC1") (pin "16") (pinfunction "VCC_16") (pintype "power_in"))
      (node (ref "IC2") (pin "4") (pinfunction "OUT_4") (pintype "passive"))
      (node (ref "J17") (pin "1") (pinfunction "VCC_1") (pintype "bidirectional"))
      (node (ref "R85") (pin "2") (pinfunction "2_2") (pintype "passive"))
      (node (ref "U1") (pin "1") (pinfunction "VCC_1") (pintype "power_in"))
      (node (ref "U10") (pin "1") (pinfunction "VCC_1") (pintype "power_in"))
      (node (ref "U11") (pin "8") (pinfunction "V+_8") (pintype "power_in"))
      (node (ref "U12") (pin "8") (pinfunction "V+_8") (pintype "power_in"))
      (node (ref "U13") (pin "1") (pinfunction "VDD_1") (pintype "bidirectional"))
      (node (ref "U13") (pin "9") (pinfunction "~{SHDN}_9") (pintype "bidirectional"))
      (node (ref "U14") (pin "1") (pinfunction "VDD_1") (pintype "bidirectional"))
      (node (ref "U14") (pin "9") (pinfunction "~{SHDN}_9") (pintype "bidirectional"))
      (node (ref "U17") (pin "8") (pinfunction "V+_8") (pintype "power_in"))
      (node (ref "U18") (pin "8") (pinfunction "V+_8") (pintype "power_in"))
      (node (ref "U19") (pin "8") (pinfunction "V+_8") (pintype "power_in"))
      (node (ref "U2") (pin "1") (pinfunction "VCC_1") (pintype "power_in"))
      (node (ref "U20") (pin "8") (pinfunction "V+_8") (pintype "power_in"))
      (node (ref "U21") (pin "1") (pinfunction "VDD_1_1") (pintype "power_in"))
      (node (ref "U21") (pin "24") (pinfunction "VDD_2_24") (pintype "power_in"))
      (node (ref "U21") (pin "48") (pinfunction "VDD_3_48") (pintype "power_in"))
      (node (ref "U21") (pin "9") (pinfunction "VDDA_9") (pintype "power_in"))
      (node (ref "U3") (pin "8") (pinfunction "V+_8") (pintype "power_in"))
      (node (ref "U4") (pin "8") (pinfunction "V+_8") (pintype "power_in"))
      (node (ref "U5") (pin "1") (pinfunction "VDD_1") (pintype "bidirectional"))
      (node (ref "U5") (pin "9") (pinfunction "~{SHDN}_9") (pintype "bidirectional"))
      (node (ref "U6") (pin "1") (pinfunction "VDD_1") (pintype "bidirectional"))
      (node (ref "U6") (pin "9") (pinfunction "~{SHDN}_9") (pintype "bidirectional"))
      (node (ref "U9") (pin "1") (pinfunction "VCC_1") (pintype "power_in"))
      (node (ref "VR1") (pin "3") (pinfunction "E_3") (pintype "passive"))
      (node (ref "VR2") (pin "3") (pinfunction "E_3") (pintype "passive"))
      (node (ref "VR3") (pin "3") (pinfunction "E_3") (pintype "passive"))
      (node (ref "VR4") (pin "3") (pinfunction "E_3") (pintype "passive"))
      (node (ref "VR5") (pin "3") (pinfunction "E_3") (pintype "passive"))
      (node (ref "VR6") (pin "3") (pinfunction "E_3") (pintype "passive"))
      (node (ref "VR7") (pin "3") (pinfunction "E_3") (pintype "passive"))
      (node (ref "VR8") (pin "3") (pinfunction "E_3") (pintype "passive"))
    )
    (net (code "2") (name "+12V") (class "Default")
      (node (ref "C1") (pin "1") (pinfunction "1_1") (pintype "passive"))
      (node (ref "C3") (pin "1") (pinfunction "1_1") (pintype "passive"))
      (node (ref "C35") (pin "1") (pinfunction "1_1") (pintype "passive"))
      (node (ref "C37") (pin "+") (pinfunction "+_+") (pintype "passive"))
      (node (ref "C39") (pin "+") (pinfunction "+_+") (pintype "passive"))
      (node (ref "C48") (pin "1") (pinfunction "1_1") (pintype "passive"))
      (node (ref "C5") (pin "1") (pinfunction "1_1") (pintype "passive"))
      (node (ref "C7") (pin "1") (pinfunction "1_1") (pintype "passive"))
      (node (ref "D1") (pin "C") (pinfunction "C_C") (pintype "passive"))
      (node (ref "IC2") (pin "3") (pinfunction "IN_3") (pintype "input"))
      (node (ref "U15") (pin "8") (pinfunction "V+_8") (pintype "power_in"))
      (node (ref "U16") (pin "8") (pinfunction "V+_8") (pintype "power_in"))
      (node (ref "U22") (pin "8") (pinfunction "V+_8") (pintype "power_in"))
      (node (ref "U7") (pin "8") (pinfunction "V+_8") (pintype "power_in"))
      (node (ref "U8") (pin "8") (pinfunction "V+_8") (pintype "power_in"))
    )
    (net (code "3") (name "-12V") (class "Default")
      (node (ref "C2") (pin "2") (pinfunction "2_2") (pintype "passive"))
      (node (ref "C34") (pin "2") (pinfunction "2_2") (pintype "passive"))
      (node (ref "C38") (pin "-") (pinfunction "-_-") (pintype "passive"))
      (node (ref "C4") (pin "2") (pinfunction "2_2") (pintype "passive"))
      (node (ref "C47") (pin "2") (pinfunction "2_2") (pintype "passive"))
      (node (ref "C6") (pin "2") (pinfunction "2_2") (pintype "passive"))
      (node (ref "C8") (pin "2") (pinfunction "2_2") (pintype "passive"))
      (node (ref "D2") (pin "A") (pinfunction "A_A") (pintype "passive"))
      (node (ref "R90") (pin "2") (pinfunction "2_2") (pintype "passive"))
      (node (ref "U15") (pin "4") (pinfunction "V-_4") (pintype "power_in"))
      (node (ref "U16") (pin "4") (pinfunction "V-_4") (pintype "power_in"))
      (node (ref "U22") (pin "4") (pinfunction "V-_4") (pintype "power_in"))
      (node (ref "U7") (pin "4") (pinfunction "V-_4") (pintype "power_in"))
      (node (ref "U8") (pin "4") (pinfunction "V-_4") (pintype "power_in"))
    )
    (net (code "4") (name "1_IN_L") (class "Default")
      (node (ref "J1") (pin "P$1_TIP") (pinfunction "2_P$1_TIP") (pintype "passive"))
      (node (ref "J2") (pin "P$2_SWITCH") (pinfunction "3_P$2_SWITCH") (pintype "passive"))
      (node (ref "R2") (pin "1") (pinfunction "1_1") (pintype "passive"))
    )
    (net (code "5") (name "1_IN_R") (class "Default")
      (node (ref "J2") (pin "P$1_TIP") (pinfunction "2_P$1_TIP") (pintype "passive"))
      (node (ref "R4") (pin "1") (pinfunction "1_1") (pintype "passive"))
    )
    (net (code "6") (name "2_IN_L") (class "Default")
      (node (ref "J3") (pin "P$1_TIP") (pinfunction "2_P$1_TIP") (pintype "passive"))
      (node (ref "J4") (pin "P$2_SWITCH") (pinfunction "3_P$2_SWITCH") (pintype "passive"))
      (node (ref "R6") (pin "1") (pinfunction "1_1") (pintype "passive"))
    )
    (net (code "7") (name "2_IN_R") (class "Default")
      (node (ref "J4") (pin "P$1_TIP") (pinfunction "2_P$1_TIP") (pintype "passive"))
      (node (ref "R8") (pin "1") (pinfunction "1_1") (pintype "passive"))
    )
    (net (code "8") (name "3_IN_L") (class "Default")
      (node (ref "J5") (pin "P$1_TIP") (pinfunction "2_P$1_TIP") (pintype "passive"))
      (node (ref "J6") (pin "P$2_SWITCH") (pinfunction "3_P$2_SWITCH") (pintype "passive"))
      (node (ref "R34") (pin "1") (pinfunction "1_1") (pintype "passive"))
    )
    (net (code "9") (name "3_IN_R") (class "Default")
      (node (ref "J6") (pin "P$1_TIP") (pinfunction "2_P$1_TIP") (pintype "passive"))
      (node (ref "R36") (pin "1") (pinfunction "1_1") (pintype "passive"))
    )
    (net (code "10") (name "4_IN_L") (class "Default")
      (node (ref "J7") (pin "P$1_TIP") (pinfunction "2_P$1_TIP") (pintype "passive"))
      (node (ref "J8") (pin "P$2_SWITCH") (pinfunction "3_P$2_SWITCH") (pintype "passive"))
      (node (ref "R38") (pin "1") (pinfunction "1_1") (pintype "passive"))
    )
    (net (code "11") (name "4_IN_R") (class "Default")
      (node (ref "J8") (pin "P$1_TIP") (pinfunction "2_P$1_TIP") (pintype "passive"))
      (node (ref "R40") (pin "1") (pinfunction "1_1") (pintype "passive"))
    )
    (net (code "12") (name "AREF_-10") (class "Default")
      (node (ref "C40") (pin "1") (pinfunction "1_1") (pintype "passive"))
      (node (ref "D3") (pin "2") (pinfunction "A_2") (pintype "passive"))
      (node (ref "R1") (pin "1") (pinfunction "1_1") (pintype "passive"))
      (node (ref "R101") (pin "1") (pinfunction "1_1") (pintype "passive"))
      (node (ref "R3") (pin "1") (pinfunction "1_1") (pintype "passive"))
      (node (ref "R33") (pin "1") (pinfunction "1_1") (pintype "passive"))
      (node (ref "R35") (pin "1") (pinfunction "1_1") (pintype "passive"))
      (node (ref "R37") (pin "1") (pinfunction "1_1") (pintype "passive"))
      (node (ref "R39") (pin "1") (pinfunction "1_1") (pintype "passive"))
      (node (ref "R5") (pin "1") (pinfunction "1_1") (pintype "passive"))
      (node (ref "R65") (pin "1") (pinfunction "1_1") (pintype "passive"))
      (node (ref "R67") (pin "1") (pinfunction "1_1") (pintype "passive"))
      (node (ref "R69") (pin "1") (pinfunction "1_1") (pintype "passive"))
      (node (ref "R7") (pin "1") (pinfunction "1_1") (pintype "passive"))
      (node (ref "R71") (pin "1") (pinfunction "1_1") (pintype "passive"))
      (node (ref "R81") (pin "1") (pinfunction "1_1") (pintype "passive"))
      (node (ref "R82") (pin "1") (pinfunction "1_1") (pintype "passive"))
      (node (ref "R83") (pin "1") (pinfunction "1_1") (pintype "passive"))
      (node (ref "R90") (pin "1") (pinfunction "1_1") (pintype "passive"))
    )
    (net (code "13") (name "BIAS_DAC1_L") (class "Default")
      (node (ref "R16") (pin "1") (pinfunction "1_1") (pintype "passive"))
      (node (ref "U1") (pin "8") (pinfunction "VOUTA_8") (pintype "output"))
    )
    (net (code "14") (name "BIAS_DAC1_R") (class "Default")
      (node (ref "R15") (pin "1") (pinfunction "1_1") (pintype "passive"))
      (node (ref "U1") (pin "6") (pinfunction "VOUTB_6") (pintype "output"))
    )
    (net (code "15") (name "BIAS_DAC2_L") (class "Default")
      (node (ref "R20") (pin "1") (pinfunction "1_1") (pintype "passive"))
      (node (ref "U2") (pin "8") (pinfunction "VOUTA_8") (pintype "output"))
    )
    (net (code "16") (name "BIAS_DAC2_R") (class "Default")
      (node (ref "R19") (pin "1") (pinfunction "1_1") (pintype "passive"))
      (node (ref "U2") (pin "6") (pinfunction "VOUTB_6") (pintype "output"))
    )
    (net (code "17") (name "BIAS_DAC3_L") (class "Default")
      (node (ref "R51") (pin "1") (pinfunction "1_1") (pintype "passive"))
      (node (ref "U9") (pin "8") (pinfunction "VOUTA_8") (pintype "output"))
    )
    (net (code "18") (name "BIAS_DAC3_R") (class "Default")
      (node (ref "R47") (pin "1") (pinfunction "1_1") (pintype "passive"))
      (node (ref "U9") (pin "6") (pinfunction "VOUTB_6") (pintype "output"))
    )
    (net (code "19") (name "BIAS_DAC4_L") (class "Default")
      (node (ref "R52") (pin "1") (pinfunction "1_1") (pintype "passive"))
      (node (ref "U10") (pin "8") (pinfunction "VOUTA_8") (pintype "output"))
    )
    (net (code "20") (name "BIAS_DAC4_R") (class "Default")
      (node (ref "R50") (pin "1") (pinfunction "1_1") (pintype "passive"))
      (node (ref "U10") (pin "6") (pinfunction "VOUTB_6") (pintype "output"))
    )
    (net (code "21") (name "CS_BIAS_DAC_1") (class "Default")
      (node (ref "U1") (pin "2") (pinfunction "CS_2") (pintype "input"))
      (node (ref "U21") (pin "45") (pinfunction "PB8/I2C1_SCL/TIM16_CH1_45") (pintype "power_in"))
    )
    (net (code "22") (name "CS_BIAS_DAC_2") (class "Default")
      (node (ref "U2") (pin "2") (pinfunction "CS_2") (pintype "input"))
      (node (ref "U21") (pin "46") (pinfunction "PB9/I2C1_SDA/IR_OUT/SPI2_NSS/TIM17_CH1/EVENTOUT_46") (pintype "power_in"))
    )
    (net (code "23") (name "CS_BIAS_DAC_3") (class "Default")
      (node (ref "U21") (pin "21") (pinfunction "PB10/I2C2_SCL_21") (pintype "bidirectional"))
      (node (ref "U9") (pin "2") (pinfunction "CS_2") (pintype "input"))
    )
    (net (code "24") (name "CS_BIAS_DAC_4") (class "Default")
      (node (ref "U10") (pin "2") (pinfunction "CS_2") (pintype "input"))
      (node (ref "U21") (pin "22") (pinfunction "PB11/I2C2_SDA/EVENTOUT_22") (pintype "bidirectional"))
    )
    (net (code "25") (name "CS_DAC_1") (class "Default")
      (node (ref "U21") (pin "38") (pinfunction "PA15/SPI1_NSS/USART2_RX/EVENTOUT_38") (pintype "bidirectional"))
      (node (ref "U5") (pin "3") (pinfunction "~{CS}_3") (pintype "bidirectional"))
    )
    (net (code "26") (name "CS_DAC_2") (class "Default")
      (node (ref "U21") (pin "43") (pinfunction "PB7/I2C1_SDA/USART1_RX/TIM17_CH1N_43") (pintype "bidirectional"))
      (node (ref "U6") (pin "3") (pinfunction "~{CS}_3") (pintype "bidirectional"))
    )
    (net (code "27") (name "CS_DAC_3") (class "Default")
      (node (ref "U13") (pin "3") (pinfunction "~{CS}_3") (pintype "bidirectional"))
      (node (ref "U21") (pin "28") (pinfunction "PB15/SPI2_MOSI/TIM1_CH3N/TIM15_CH1N/TIM15_CH2/RTC_REFIN_28") (pintype "bidirectional"))
    )
    (net (code "28") (name "CS_DAC_4") (class "Default")
      (node (ref "U14") (pin "3") (pinfunction "~{CS}_3") (pintype "bidirectional"))
      (node (ref "U21") (pin "2") (pinfunction "PC13/RTC_TAMP1/RTC_TS/RTC_OUT/WKUP2_2") (pintype "bidirectional"))
    )
    (net (code "29") (name "GND") (class "Default")
      (node (ref "C1") (pin "2") (pinfunction "2_2") (pintype "passive"))
      (node (ref "C10") (pin "2") (pinfunction "2_2") (pintype "passive"))
      (node (ref "C11") (pin "2") (pinfunction "2_2") (pintype "passive"))
      (node (ref "C12") (pin "2") (pinfunction "2_2") (pintype "passive"))
      (node (ref "C13") (pin "2") (pinfunction "2_2") (pintype "passive"))
      (node (ref "C14") (pin "2") (pinfunction "2_2") (pintype "passive"))
      (node (ref "C15") (pin "2") (pinfunction "2_2") (pintype "passive"))
      (node (ref "C16") (pin "2") (pinfunction "2_2") (pintype "passive"))
      (node (ref "C17") (pin "2") (pinfunction "2_2") (pintype "passive"))
      (node (ref "C18") (pin "2") (pinfunction "2_2") (pintype "passive"))
      (node (ref "C2") (pin "1") (pinfunction "1_1") (pintype "passive"))
      (node (ref "C23") (pin "2") (pinfunction "2_2") (pintype "passive"))
      (node (ref "C24") (pin "2") (pinfunction "2_2") (pintype "passive"))
      (node (ref "C25") (pin "2") (pinfunction "2_2") (pintype "passive"))
      (node (ref "C26") (pin "1") (pinfunction "1_1") (pintype "passive"))
      (node (ref "C27") (pin "1") (pinfunction "1_1") (pintype "passive"))
      (node (ref "C28") (pin "2") (pinfunction "2_2") (pintype "passive"))
      (node (ref "C29") (pin "2") (pinfunction "2_2") (pintype "passive"))
      (node (ref "C3") (pin "2") (pinfunction "2_2") (pintype "passive"))
      (node (ref "C30") (pin "2") (pinfunction "2_2") (pintype "passive"))
      (node (ref "C31") (pin "2") (pinfunction "2_2") (pintype "passive"))
      (node (ref "C34") (pin "1") (pinfunction "1_1") (pintype "passive"))
      (node (ref "C35") (pin "2") (pinfunction "2_2") (pintype "passive"))
      (node (ref "C36") (pin "GND1") (pinfunction "GND_GND1") (pintype "bidirectional"))
      (node (ref "C36") (pin "GND2") (pinfunction "GND_GND2") (pintype "bidirectional"))
      (node (ref "C36") (pin "GND3") (pinfunction "GND_GND3") (pintype "bidirectional"))
      (node (ref "C36") (pin "GND4") (pinfunction "GND_GND4") (pintype "bidirectional"))
      (node (ref "C36") (pin "GND5") (pinfunction "GND_GND5") (pintype "bidirectional"))
      (node (ref "C36") (pin "GND6") (pinfunction "GND_GND6") (pintype "bidirectional"))
      (node (ref "C37") (pin "-") (pinfunction "-_-") (pintype "passive"))
      (node (ref "C38") (pin "+") (pinfunction "+_+") (pintype "passive"))
      (node (ref "C39") (pin "-") (pinfunction "-_-") (pintype "passive"))
      (node (ref "C4") (pin "1") (pinfunction "1_1") (pintype "passive"))
      (node (ref "C40") (pin "2") (pinfunction "2_2") (pintype "passive"))
      (node (ref "C41") (pin "-") (pinfunction "-_-") (pintype "passive"))
      (node (ref "C42") (pin "2") (pinfunction "2_2") (pintype "passive"))
      (node (ref "C43") (pin "2") (pinfunction "2_2") (pintype "passive"))
      (node (ref "C44") (pin "2") (pinfunction "2_2") (pintype "passive"))
      (node (ref "C45") (pin "2") (pinfunction "2_2") (pintype "passive"))
      (node (ref "C46") (pin "2") (pinfunction "2_2") (pintype "passive"))
      (node (ref "C47") (pin "1") (pinfunction "1_1") (pintype "passive"))
      (node (ref "C48") (pin "2") (pinfunction "2_2") (pintype "passive"))
      (node (ref "C49") (pin "2") (pinfunction "2_2") (pintype "passive"))
      (node (ref "C5") (pin "2") (pinfunction "2_2") (pintype "passive"))
      (node (ref "C50") (pin "2") (pinfunction "2_2") (pintype "passive"))
      (node (ref "C51") (pin "2") (pinfunction "2_2") (pintype "passive"))
      (node (ref "C52") (pin "2") (pinfunction "2_2") (pintype "passive"))
      (node (ref "C53") (pin "2") (pinfunction "2_2") (pintype "passive"))
      (node (ref "C54") (pin "2") (pinfunction "2_2") (pintype "passive"))
      (node (ref "C55") (pin "2") (pinfunction "2_2") (pintype "passive"))
      (node (ref "C56") (pin "2") (pinfunction "2_2") (pintype "passive"))
      (node (ref "C57") (pin "2") (pinfunction "2_2") (pintype "passive"))
      (node (ref "C58") (pin "2") (pinfunction "2_2") (pintype "passive"))
      (node (ref "C59") (pin "2") (pinfunction "2_2") (pintype "passive"))
      (node (ref "C6") (pin "1") (pinfunction "1_1") (pintype "passive"))
      (node (ref "C60") (pin "2") (pinfunction "2_2") (pintype "passive"))
      (node (ref "C61") (pin "2") (pinfunction "2_2") (pintype "passive"))
      (node (ref "C62") (pin "2") (pinfunction "2_2") (pintype "passive"))
      (node (ref "C63") (pin "2") (pinfunction "2_2") (pintype "passive"))
      (node (ref "C64") (pin "2") (pinfunction "2_2") (pintype "passive"))
      (node (ref "C7") (pin "2") (pinfunction "2_2") (pintype "passive"))
      (node (ref "C8") (pin "1") (pinfunction "1_1") (pintype "passive"))
      (node (ref "C9") (pin "2") (pinfunction "2_2") (pintype "passive"))
      (node (ref "D3") (pin "1") (pinfunction "C_1") (pintype "passive"))
      (node (ref "IC1") (pin "6") (pinfunction "INH_6") (pintype "input"))
      (node (ref "IC1") (pin "7") (pinfunction "VEE_7") (pintype "power_in"))
      (node (ref "IC1") (pin "8") (pinfunction "GND_8") (pintype "power_in"))
      (node (ref "IC2") (pin "1") (pinfunction "ADJ_1") (pintype "input"))
      (node (ref "J1") (pin "P$3_SLEEVE") (pinfunction "1_P$3_SLEEVE") (pintype "passive"))
      (node (ref "J10") (pin "P$3_SLEEVE") (pinfunction "1_P$3_SLEEVE") (pintype "passive"))
      (node (ref "J11") (pin "P$3_SLEEVE") (pinfunction "1_P$3_SLEEVE") (pintype "passive"))
      (node (ref "J12") (pin "P$3_SLEEVE") (pinfunction "1_P$3_SLEEVE") (pintype "passive"))
      (node (ref "J13") (pin "P$3_SLEEVE") (pinfunction "1_P$3_SLEEVE") (pintype "passive"))
      (node (ref "J14") (pin "P$3_SLEEVE") (pinfunction "1_P$3_SLEEVE") (pintype "passive"))
      (node (ref "J15") (pin "P$3_SLEEVE") (pinfunction "1_P$3_SLEEVE") (pintype "passive"))
      (node (ref "J16") (pin "P$3_SLEEVE") (pinfunction "1_P$3_SLEEVE") (pintype "passive"))
      (node (ref "J17") (pin "3") (pinfunction "GND_3") (pintype "bidirectional"))
      (node (ref "J17") (pin "5") (pinfunction "GND_5") (pintype "bidirectional"))
      (node (ref "J17") (pin "9") (pinfunction "GNDDTCT_9") (pintype "bidirectional"))
      (node (ref "J18") (pin "P$3_SLEEVE") (pinfunction "1_P$3_SLEEVE") (pintype "passive"))
      (node (ref "J19") (pin "P$3_SLEEVE") (pinfunction "1_P$3_SLEEVE") (pintype "passive"))
      (node (ref "J2") (pin "P$3_SLEEVE") (pinfunction "1_P$3_SLEEVE") (pintype "passive"))
      (node (ref "J3") (pin "P$3_SLEEVE") (pinfunction "1_P$3_SLEEVE") (pintype "passive"))
      (node (ref "J4") (pin "P$3_SLEEVE") (pinfunction "1_P$3_SLEEVE") (pintype "passive"))
      (node (ref "J5") (pin "P$3_SLEEVE") (pinfunction "1_P$3_SLEEVE") (pintype "passive"))
      (node (ref "J6") (pin "P$3_SLEEVE") (pinfunction "1_P$3_SLEEVE") (pintype "passive"))
      (node (ref "J7") (pin "P$3_SLEEVE") (pinfunction "1_P$3_SLEEVE") (pintype "passive"))
      (node (ref "J8") (pin "P$3_SLEEVE") (pinfunction "1_P$3_SLEEVE") (pintype "passive"))
      (node (ref "J9") (pin "P$3_SLEEVE") (pinfunction "1_P$3_SLEEVE") (pintype "passive"))
      (node (ref "R21") (pin "1") (pinfunction "1_1") (pintype "passive"))
      (node (ref "R22") (pin "2") (pinfunction "2_2") (pintype "passive"))
      (node (ref "R24") (pin "2") (pinfunction "2_2") (pintype "passive"))
      (node (ref "R27") (pin "2") (pinfunction "2_2") (pintype "passive"))
      (node (ref "R53") (pin "1") (pinfunction "1_1") (pintype "passive"))
      (node (ref "R54") (pin "1") (pinfunction "1_1") (pintype "passive"))
      (node (ref "R55") (pin "1") (pinfunction "1_1") (pintype "passive"))
      (node (ref "R56") (pin "1") (pinfunction "1_1") (pintype "passive"))
      (node (ref "R86") (pin "1") (pinfunction "1_1") (pintype "passive"))
      (node (ref "R87") (pin "1") (pinfunction "1_1") (pintype "passive"))
      (node (ref "S1") (pin "3") (pinfunction "3_3") (pintype "passive"))
      (node (ref "S1") (pin "4") (pinfunction "4_4") (pintype "passive"))
      (node (ref "S2") (pin "3") (pinfunction "3_3") (pintype "passive"))
      (node (ref "S2") (pin "4") (pinfunction "4_4") (pintype "passive"))
      (node (ref "S3") (pin "3") (pinfunction "3_3") (pintype "passive"))
      (node (ref "S3") (pin "4") (pinfunction "4_4") (pintype "passive"))
      (node (ref "S4") (pin "1") (pinfunction "1_1") (pintype "passive"))
      (node (ref "S4") (pin "2") (pinfunction "2_2") (pintype "passive"))
      (node (ref "U1") (pin "5") (pinfunction "LDAC_5") (pintype "input"))
      (node (ref "U1") (pin "7") (pinfunction "GND_7") (pintype "power_in"))
      (node (ref "U10") (pin "5") (pinfunction "LDAC_5") (pintype "input"))
      (node (ref "U10") (pin "7") (pinfunction "GND_7") (pintype "power_in"))
      (node (ref "U11") (pin "3") (pinfunction "+IN_3") (pintype "input"))
      (node (ref "U11") (pin "4") (pinfunction "V-_4") (pintype "power_in"))
      (node (ref "U11") (pin "5") (pinfunction "+IN_5") (pintype "input"))
      (node (ref "U12") (pin "3") (pinfunction "+IN_3") (pintype "input"))
      (node (ref "U12") (pin "4") (pinfunction "V-_4") (pintype "power_in"))
      (node (ref "U12") (pin "5") (pinfunction "+IN_5") (pintype "input"))
      (node (ref "U13") (pin "12") (pinfunction "VSS_12") (pintype "bidirectional"))
      (node (ref "U13") (pin "8") (pinfunction "~{LDAC}_8") (pintype "bidirectional"))
      (node (ref "U14") (pin "12") (pinfunction "VSS_12") (pintype "bidirectional"))
      (node (ref "U14") (pin "8") (pinfunction "~{LDAC}_8") (pintype "bidirectional"))
      (node (ref "U17") (pin "3") (pinfunction "+IN_3") (pintype "input"))
      (node (ref "U17") (pin "4") (pinfunction "V-_4") (pintype "power_in"))
      (node (ref "U17") (pin "5") (pinfunction "+IN_5") (pintype "input"))
      (node (ref "U18") (pin "3") (pinfunction "+IN_3") (pintype "input"))
      (node (ref "U18") (pin "4") (pinfunction "V-_4") (pintype "power_in"))
      (node (ref "U18") (pin "5") (pinfunction "+IN_5") (pintype "input"))
      (node (ref "U19") (pin "3") (pinfunction "+IN_3") (pintype "input"))
      (node (ref "U19") (pin "4") (pinfunction "V-_4") (pintype "power_in"))
      (node (ref "U19") (pin "5") (pinfunction "+IN_5") (pintype "input"))
      (node (ref "U2") (pin "5") (pinfunction "LDAC_5") (pintype "input"))
      (node (ref "U2") (pin "7") (pinfunction "GND_7") (pintype "power_in"))
      (node (ref "U20") (pin "3") (pinfunction "+IN_3") (pintype "input"))
      (node (ref "U20") (pin "4") (pinfunction "V-_4") (pintype "power_in"))
      (node (ref "U20") (pin "5") (pinfunction "+IN_5") (pintype "input"))
      (node (ref "U21") (pin "23") (pinfunction "VSS_1_23") (pintype "power_in"))
      (node (ref "U21") (pin "44") (pinfunction "BOOT0_44") (pintype "bidirectional"))
      (node (ref "U21") (pin "47") (pinfunction "VSS_2_47") (pintype "power_in"))
      (node (ref "U21") (pin "8") (pinfunction "VSSA_8") (pintype "power_in"))
      (node (ref "U22") (pin "3") (pinfunction "+IN_3") (pintype "input"))
      (node (ref "U22") (pin "5") (pinfunction "+IN_5") (pintype "input"))
      (node (ref "U3") (pin "3") (pinfunction "+IN_3") (pintype "input"))
      (node (ref "U3") (pin "4") (pinfunction "V-_4") (pintype "power_in"))
      (node (ref "U3") (pin "5") (pinfunction "+IN_5") (pintype "input"))
      (node (ref "U4") (pin "3") (pinfunction "+IN_3") (pintype "input"))
      (node (ref "U4") (pin "4") (pinfunction "V-_4") (pintype "power_in"))
      (node (ref "U4") (pin "5") (pinfunction "+IN_5") (pintype "input"))
      (node (ref "U5") (pin "12") (pinfunction "VSS_12") (pintype "bidirectional"))
      (node (ref "U5") (pin "8") (pinfunction "~{LDAC}_8") (pintype "bidirectional"))
      (node (ref "U6") (pin "12") (pinfunction "VSS_12") (pintype "bidirectional"))
      (node (ref "U6") (pin "8") (pinfunction "~{LDAC}_8") (pintype "bidirectional"))
      (node (ref "U9") (pin "5") (pinfunction "LDAC_5") (pintype "input"))
      (node (ref "U9") (pin "7") (pinfunction "GND_7") (pintype "power_in"))
      (node (ref "VR1") (pin "1") (pinfunction "A_1") (pintype "passive"))
      (node (ref "VR2") (pin "1") (pinfunction "A_1") (pintype "passive"))
      (node (ref "VR3") (pin "1") (pinfunction "A_1") (pintype "passive"))
      (node (ref "VR4") (pin "1") (pinfunction "A_1") (pintype "passive"))
      (node (ref "VR5") (pin "1") (pinfunction "A_1") (pintype "passive"))
      (node (ref "VR6") (pin "1") (pinfunction "A_1") (pintype "passive"))
      (node (ref "VR7") (pin "1") (pinfunction "A_1") (pintype "passive"))
      (node (ref "VR8") (pin "1") (pinfunction "A_1") (pintype "passive"))
    )
    (net (code "30") (name "LED_1") (class "Default")
      (node (ref "R91") (pin "1") (pinfunction "1_1") (pintype "passive"))
      (node (ref "U21") (pin "29") (pinfunction "PA8/USART1_CK/TIM1_CH1/EVENTOUT/MCO_29") (pintype "bidirectional"))
    )
    (net (code "31") (name "LED_1_N") (class "Default")
      (node (ref "U$1") (pin "2") (pinfunction "2_2") (pintype "bidirectional"))
      (node (ref "U21") (pin "3") (pinfunction "PC14/OSC32_IN_3") (pintype "bidirectional"))
    )
    (net (code "32") (name "LED_2") (class "Default")
      (node (ref "R92") (pin "1") (pinfunction "1_1") (pintype "passive"))
      (node (ref "U21") (pin "30") (pinfunction "PA9/USART1_TX/TIM1_CH2/TIM15_BKIN_30") (pintype "bidirectional"))
    )
    (net (code "33") (name "LED_2_N") (class "Default")
      (node (ref "U$2") (pin "2") (pinfunction "2_2") (pintype "bidirectional"))
      (node (ref "U21") (pin "4") (pinfunction "PC15/OSC32_OUT_4") (pintype "bidirectional"))
    )
    (net (code "34") (name "LED_3") (class "Default")
      (node (ref "R93") (pin "1") (pinfunction "1_1") (pintype "passive"))
      (node (ref "U21") (pin "31") (pinfunction "PA10/USART1_RX/TIM1_CH3/TIM17_BKIN_31") (pintype "bidirectional"))
    )
    (net (code "35") (name "LED_3_N") (class "Default")
      (node (ref "U$3") (pin "2") (pinfunction "2_2") (pintype "bidirectional"))
      (node (ref "U21") (pin "35") (pinfunction "PF6/I2C2_SCL_35") (pintype "bidirectional"))
    )
    (net (code "36") (name "LED_4") (class "Default")
      (node (ref "R94") (pin "1") (pinfunction "1_1") (pintype "passive"))
      (node (ref "U21") (pin "32") (pinfunction "PA11/USART1_CTS/TIM1_CH4/EVENTOUT_32") (pintype "bidirectional"))
    )
    (net (code "37") (name "LED_4_N") (class "Default")
      (node (ref "U$4") (pin "2") (pinfunction "2_2") (pintype "bidirectional"))
      (node (ref "U21") (pin "36") (pinfunction "PF7/I2C2_SDA_36") (pintype "bidirectional"))
    )
    (net (code "38") (name "MISO") (class "Default")
      (node (ref "U21") (pin "40") (pinfunction "PB4/SPI1_MISO/TIM3_CH1/EVENTOUT_40") (pintype "bidirectional"))
    )
    (net (code "39") (name "MOSI") (class "Default")
      (node (ref "U1") (pin "4") (pinfunction "SDI_4") (pintype "input"))
      (node (ref "U10") (pin "4") (pinfunction "SDI_4") (pintype "input"))
      (node (ref "U13") (pin "5") (pinfunction "SDI_5") (pintype "bidirectional"))
      (node (ref "U14") (pin "5") (pinfunction "SDI_5") (pintype "bidirectional"))
      (node (ref "U2") (pin "4") (pinfunction "SDI_4") (pintype "input"))
      (node (ref "U21") (pin "41") (pinfunction "PB5/SPI1_MOSI/I2C1_SMBA/TIM16_BKIN/TIM3_CH2_41") (pintype "bidirectional"))
      (node (ref "U5") (pin "5") (pinfunction "SDI_5") (pintype "bidirectional"))
      (node (ref "U6") (pin "5") (pinfunction "SDI_5") (pintype "bidirectional"))
      (node (ref "U9") (pin "4") (pinfunction "SDI_4") (pintype "input"))
    )
    (net (code "40") (name "MUX_ADDR_0") (class "Default")
      (node (ref "IC1") (pin "11") (pinfunction "A_11") (pintype "input"))
      (node (ref "U21") (pin "25") (pinfunction "PB12/SPI2_NSS/TIM1_BKIN/EVENTOUT_25") (pintype "bidirectional"))
    )
    (net (code "41") (name "MUX_ADDR_1") (class "Default")
      (node (ref "IC1") (pin "10") (pinfunction "B_10") (pintype "input"))
      (node (ref "U21") (pin "26") (pinfunction "PB13/SPI2_SCK/TIM1_CH1N_26") (pintype "bidirectional"))
    )
    (net (code "42") (name "MUX_ADDR_2") (class "Default")
      (node (ref "IC1") (pin "9") (pinfunction "C_9") (pintype "input"))
      (node (ref "U21") (pin "27") (pinfunction "PB14/SPI2_MISO/TIM1_CH2N/TIM15_CH1_27") (pintype "bidirectional"))
    )
    (net (code "43") (name "NRST") (class "Default")
      (node (ref "J17") (pin "10") (pinfunction "~{RESET}_10") (pintype "bidirectional"))
      (node (ref "R85") (pin "1") (pinfunction "1_1") (pintype "passive"))
      (node (ref "U21") (pin "7") (pinfunction "NRST_7") (pintype "bidirectional"))
    )
    (net (code "44") (name "Net-(C36-+12V-PadPOS1)") (class "Default")
      (node (ref "C36") (pin "POS1") (pinfunction "+12V_POS1") (pintype "bidirectional"))
      (node (ref "C36") (pin "POS2") (pinfunction "+12V_POS2") (pintype "bidirectional"))
      (node (ref "D1") (pin "A") (pinfunction "A_A") (pintype "passive"))
    )
    (net (code "45") (name "Net-(C36--12V-PadNEG1)") (class "Default")
      (node (ref "C36") (pin "NEG1") (pinfunction "-12V_NEG1") (pintype "bidirectional"))
      (node (ref "C36") (pin "NEG2") (pinfunction "-12V_NEG2") (pintype "bidirectional"))
      (node (ref "D2") (pin "C") (pinfunction "C_C") (pintype "passive"))
    )
    (net (code "46") (name "Net-(C65-Pad-)") (class "Default")
      (node (ref "C65") (pin "-") (pinfunction "-_-") (pintype "passive"))
      (node (ref "R86") (pin "2") (pinfunction "2_2") (pintype "passive"))
      (node (ref "R95") (pin "1") (pinfunction "1_1") (pintype "passive"))
    )
    (net (code "47") (name "Net-(C66-Pad-)") (class "Default")
      (node (ref "C66") (pin "-") (pinfunction "-_-") (pintype "passive"))
      (node (ref "R87") (pin "2") (pinfunction "2_2") (pintype "passive"))
      (node (ref "R96") (pin "1") (pinfunction "1_1") (pintype "passive"))
    )
    (net (code "48") (name "Net-(J9-2)") (class "Default")
      (node (ref "J9") (pin "P$1_TIP") (pinfunction "2_P$1_TIP") (pintype "passive"))
      (node (ref "R66") (pin "1") (pinfunction "1_1") (pintype "passive"))
    )
    (net (code "49") (name "Net-(J10-2)") (class "Default")
      (node (ref "J10") (pin "P$1_TIP") (pinfunction "2_P$1_TIP") (pintype "passive"))
      (node (ref "R68") (pin "1") (pinfunction "1_1") (pintype "passive"))
    )
    (net (code "50") (name "Net-(J11-2)") (class "Default")
      (node (ref "J11") (pin "P$1_TIP") (pinfunction "2_P$1_TIP") (pintype "passive"))
      (node (ref "R70") (pin "1") (pinfunction "1_1") (pintype "passive"))
    )
    (net (code "51") (name "Net-(J12-2)") (class "Default")
      (node (ref "J12") (pin "P$1_TIP") (pinfunction "2_P$1_TIP") (pintype "passive"))
      (node (ref "R72") (pin "1") (pinfunction "1_1") (pintype "passive"))
    )
    (net (code "52") (name "Net-(J13-2)") (class "Default")
      (node (ref "J13") (pin "P$1_TIP") (pinfunction "2_P$1_TIP") (pintype "passive"))
      (node (ref "R77") (pin "2") (pinfunction "2_2") (pintype "passive"))
    )
    (net (code "53") (name "Net-(J14-2)") (class "Default")
      (node (ref "J14") (pin "P$1_TIP") (pinfunction "2_P$1_TIP") (pintype "passive"))
      (node (ref "R78") (pin "2") (pinfunction "2_2") (pintype "passive"))
    )
    (net (code "54") (name "Net-(J15-2)") (class "Default")
      (node (ref "J15") (pin "P$1_TIP") (pinfunction "2_P$1_TIP") (pintype "passive"))
      (node (ref "R79") (pin "2") (pinfunction "2_2") (pintype "passive"))
    )
    (net (code "55") (name "Net-(J16-2)") (class "Default")
      (node (ref "J16") (pin "P$1_TIP") (pinfunction "2_P$1_TIP") (pintype "passive"))
      (node (ref "R80") (pin "2") (pinfunction "2_2") (pintype "passive"))
    )
    (net (code "56") (name "Net-(J18-2)") (class "Default")
      (node (ref "J18") (pin "P$1_TIP") (pinfunction "2_P$1_TIP") (pintype "passive"))
      (node (ref "R96") (pin "2") (pinfunction "2_2") (pintype "passive"))
    )
    (net (code "57") (name "Net-(J18-3)") (class "Default")
      (node (ref "J18") (pin "P$2_SWITCH") (pinfunction "3_P$2_SWITCH") (pintype "passive"))
      (node (ref "J19") (pin "P$1_TIP") (pinfunction "2_P$1_TIP") (pintype "passive"))
      (node (ref "R95") (pin "2") (pinfunction "2_2") (pintype "passive"))
    )
    (net (code "58") (name "Net-(R91-Pad2)") (class "Default")
      (node (ref "R91") (pin "2") (pinfunction "2_2") (pintype "passive"))
      (node (ref "U$1") (pin "1") (pinfunction "1_1") (pintype "bidirectional"))
    )
    (net (code "59") (name "Net-(R92-Pad2)") (class "Default")
      (node (ref "R92") (pin "2") (pinfunction "2_2") (pintype "passive"))
      (node (ref "U$2") (pin "1") (pinfunction "1_1") (pintype "bidirectional"))
    )
    (net (code "60") (name "Net-(R93-Pad2)") (class "Default")
      (node (ref "R93") (pin "2") (pinfunction "2_2") (pintype "passive"))
      (node (ref "U$3") (pin "1") (pinfunction "1_1") (pintype "bidirectional"))
    )
    (net (code "61") (name "Net-(R94-Pad2)") (class "Default")
      (node (ref "R94") (pin "2") (pinfunction "2_2") (pintype "passive"))
      (node (ref "U$4") (pin "1") (pinfunction "1_1") (pintype "bidirectional"))
    )
    (net (code "62") (name "Net-(U3A--IN)") (class "Default")
      (node (ref "R1") (pin "2") (pinfunction "2_2") (pintype "passive"))
      (node (ref "R2") (pin "2") (pinfunction "2_2") (pintype "passive"))
      (node (ref "R9") (pin "1") (pinfunction "1_1") (pintype "passive"))
      (node (ref "U3") (pin "2") (pinfunction "-IN_2") (pintype "input"))
    )
    (net (code "63") (name "Net-(U3A-OUT)") (class "Default")
      (node (ref "R9") (pin "2") (pinfunction "2_2") (pintype "passive"))
      (node (ref "U3") (pin "1") (pinfunction "OUT_1") (pintype "output"))
      (node (ref "U5") (pin "13") (pinfunction "VREFA_13") (pintype "bidirectional"))
    )
    (net (code "64") (name "Net-(U3B--IN)") (class "Default")
      (node (ref "R10") (pin "1") (pinfunction "1_1") (pintype "passive"))
      (node (ref "R3") (pin "2") (pinfunction "2_2") (pintype "passive"))
      (node (ref "R4") (pin "2") (pinfunction "2_2") (pintype "passive"))
      (node (ref "U3") (pin "6") (pinfunction "-IN_6") (pintype "input"))
    )
    (net (code "65") (name "Net-(U3B-OUT)") (class "Default")
      (node (ref "R10") (pin "2") (pinfunction "2_2") (pintype "passive"))
      (node (ref "U3") (pin "7") (pinfunction "OUT_7") (pintype "output"))
      (node (ref "U5") (pin "11") (pinfunction "VREFB_11") (pintype "bidirectional"))
    )
    (net (code "66") (name "Net-(U4A--IN)") (class "Default")
      (node (ref "R11") (pin "1") (pinfunction "1_1") (pintype "passive"))
      (node (ref "R5") (pin "2") (pinfunction "2_2") (pintype "passive"))
      (node (ref "R6") (pin "2") (pinfunction "2_2") (pintype "passive"))
      (node (ref "U4") (pin "2") (pinfunction "-IN_2") (pintype "input"))
    )
    (net (code "67") (name "Net-(U4A-OUT)") (class "Default")
      (node (ref "R11") (pin "2") (pinfunction "2_2") (pintype "passive"))
      (node (ref "U4") (pin "1") (pinfunction "OUT_1") (pintype "output"))
      (node (ref "U6") (pin "13") (pinfunction "VREFA_13") (pintype "bidirectional"))
    )
    (net (code "68") (name "Net-(U4B--IN)") (class "Default")
      (node (ref "R12") (pin "1") (pinfunction "1_1") (pintype "passive"))
      (node (ref "R7") (pin "2") (pinfunction "2_2") (pintype "passive"))
      (node (ref "R8") (pin "2") (pinfunction "2_2") (pintype "passive"))
      (node (ref "U4") (pin "6") (pinfunction "-IN_6") (pintype "input"))
    )
    (net (code "69") (name "Net-(U4B-OUT)") (class "Default")
      (node (ref "R12") (pin "2") (pinfunction "2_2") (pintype "passive"))
      (node (ref "U4") (pin "7") (pinfunction "OUT_7") (pintype "output"))
      (node (ref "U6") (pin "11") (pinfunction "VREFB_11") (pintype "bidirectional"))
    )
    (net (code "70") (name "Net-(U5-VOUT_A)") (class "Default")
      (node (ref "R13") (pin "1") (pinfunction "1_1") (pintype "passive"))
      (node (ref "U5") (pin "14") (pinfunction "VOUT_A_14") (pintype "bidirectional"))
    )
    (net (code "71") (name "Net-(U5-VOUT_B)") (class "Default")
      (node (ref "R14") (pin "1") (pinfunction "1_1") (pintype "passive"))
      (node (ref "U5") (pin "10") (pinfunction "VOUT_B_10") (pintype "bidirectional"))
    )
    (net (code "72") (name "Net-(U6-VOUT_A)") (class "Default")
      (node (ref "R17") (pin "1") (pinfunction "1_1") (pintype "passive"))
      (node (ref "U6") (pin "14") (pinfunction "VOUT_A_14") (pintype "bidirectional"))
    )
    (net (code "73") (name "Net-(U6-VOUT_B)") (class "Default")
      (node (ref "R18") (pin "1") (pinfunction "1_1") (pintype "passive"))
      (node (ref "U6") (pin "10") (pinfunction "VOUT_B_10") (pintype "bidirectional"))
    )
    (net (code "74") (name "Net-(U7A-+IN)") (class "Default")
      (node (ref "R16") (pin "2") (pinfunction "2_2") (pintype "passive"))
      (node (ref "R24") (pin "1") (pinfunction "1_1") (pintype "passive"))
      (node (ref "U7") (pin "3") (pinfunction "+IN_3") (pintype "input"))
    )
    (net (code "75") (name "Net-(U7A--IN)") (class "Default")
      (node (ref "R13") (pin "2") (pinfunction "2_2") (pintype "passive"))
      (node (ref "R23") (pin "1") (pinfunction "1_1") (pintype "passive"))
      (node (ref "U7") (pin "2") (pinfunction "-IN_2") (pintype "input"))
    )
    (net (code "76") (name "Net-(U7A-OUT)") (class "Default")
      (node (ref "R23") (pin "2") (pinfunction "2_2") (pintype "passive"))
      (node (ref "R29") (pin "1") (pinfunction "1_1") (pintype "passive"))
      (node (ref "U7") (pin "1") (pinfunction "OUT_1") (pintype "output"))
    )
    (net (code "77") (name "Net-(U7B-+IN)") (class "Default")
      (node (ref "R15") (pin "2") (pinfunction "2_2") (pintype "passive"))
      (node (ref "R21") (pin "2") (pinfunction "2_2") (pintype "passive"))
      (node (ref "U7") (pin "5") (pinfunction "+IN_5") (pintype "input"))
    )
    (net (code "78") (name "Net-(U7B--IN)") (class "Default")
      (node (ref "R14") (pin "2") (pinfunction "2_2") (pintype "passive"))
      (node (ref "R25") (pin "1") (pinfunction "1_1") (pintype "passive"))
      (node (ref "U7") (pin "6") (pinfunction "-IN_6") (pintype "input"))
    )
    (net (code "79") (name "Net-(U7B-OUT)") (class "Default")
      (node (ref "R25") (pin "2") (pinfunction "2_2") (pintype "passive"))
      (node (ref "R30") (pin "1") (pinfunction "1_1") (pintype "passive"))
      (node (ref "U7") (pin "7") (pinfunction "OUT_7") (pintype "output"))
    )
    (net (code "80") (name "Net-(U8A-+IN)") (class "Default")
      (node (ref "R20") (pin "2") (pinfunction "2_2") (pintype "passive"))
      (node (ref "R27") (pin "1") (pinfunction "1_1") (pintype "passive"))
      (node (ref "U8") (pin "3") (pinfunction "+IN_3") (pintype "input"))
    )
    (net (code "81") (name "Net-(U8A--IN)") (class "Default")
      (node (ref "R17") (pin "2") (pinfunction "2_2") (pintype "passive"))
      (node (ref "R26") (pin "1") (pinfunction "1_1") (pintype "passive"))
      (node (ref "U8") (pin "2") (pinfunction "-IN_2") (pintype "input"))
    )
    (net (code "82") (name "Net-(U8A-OUT)") (class "Default")
      (node (ref "R26") (pin "2") (pinfunction "2_2") (pintype "passive"))
      (node (ref "R31") (pin "1") (pinfunction "1_1") (pintype "passive"))
      (node (ref "U8") (pin "1") (pinfunction "OUT_1") (pintype "output"))
    )
    (net (code "83") (name "Net-(U8B-+IN)") (class "Default")
      (node (ref "R19") (pin "2") (pinfunction "2_2") (pintype "passive"))
      (node (ref "R22") (pin "1") (pinfunction "1_1") (pintype "passive"))
      (node (ref "U8") (pin "5") (pinfunction "+IN_5") (pintype "input"))
    )
    (net (code "84") (name "Net-(U8B--IN)") (class "Default")
      (node (ref "R18") (pin "2") (pinfunction "2_2") (pintype "passive"))
      (node (ref "R28") (pin "1") (pinfunction "1_1") (pintype "passive"))
      (node (ref "U8") (pin "6") (pinfunction "-IN_6") (pintype "input"))
    )
    (net (code "85") (name "Net-(U8B-OUT)") (class "Default")
      (node (ref "R28") (pin "2") (pinfunction "2_2") (pintype "passive"))
      (node (ref "R32") (pin "1") (pinfunction "1_1") (pintype "passive"))
      (node (ref "U8") (pin "7") (pinfunction "OUT_7") (pintype "output"))
    )
    (net (code "86") (name "Net-(U11A--IN)") (class "Default")
      (node (ref "R33") (pin "2") (pinfunction "2_2") (pintype "passive"))
      (node (ref "R34") (pin "2") (pinfunction "2_2") (pintype "passive"))
      (node (ref "R41") (pin "1") (pinfunction "1_1") (pintype "passive"))
      (node (ref "U11") (pin "2") (pinfunction "-IN_2") (pintype "input"))
    )
    (net (code "87") (name "Net-(U11A-OUT)") (class "Default")
      (node (ref "R41") (pin "2") (pinfunction "2_2") (pintype "passive"))
      (node (ref "U11") (pin "1") (pinfunction "OUT_1") (pintype "output"))
      (node (ref "U13") (pin "13") (pinfunction "VREFA_13") (pintype "bidirectional"))
    )
    (net (code "88") (name "Net-(U11B--IN)") (class "Default")
      (node (ref "R35") (pin "2") (pinfunction "2_2") (pintype "passive"))
      (node (ref "R36") (pin "2") (pinfunction "2_2") (pintype "passive"))
      (node (ref "R42") (pin "1") (pinfunction "1_1") (pintype "passive"))
      (node (ref "U11") (pin "6") (pinfunction "-IN_6") (pintype "input"))
    )
    (net (code "89") (name "Net-(U11B-OUT)") (class "Default")
      (node (ref "R42") (pin "2") (pinfunction "2_2") (pintype "passive"))
      (node (ref "U11") (pin "7") (pinfunction "OUT_7") (pintype "output"))
      (node (ref "U13") (pin "11") (pinfunction "VREFB_11") (pintype "bidirectional"))
    )
    (net (code "90") (name "Net-(U12A--IN)") (class "Default")
      (node (ref "R37") (pin "2") (pinfunction "2_2") (pintype "passive"))
      (node (ref "R38") (pin "2") (pinfunction "2_2") (pintype "passive"))
      (node (ref "R43") (pin "1") (pinfunction "1_1") (pintype "passive"))
      (node (ref "U12") (pin "2") (pinfunction "-IN_2") (pintype "input"))
    )
    (net (code "91") (name "Net-(U12A-OUT)") (class "Default")
      (node (ref "R43") (pin "2") (pinfunction "2_2") (pintype "passive"))
      (node (ref "U12") (pin "1") (pinfunction "OUT_1") (pintype "output"))
      (node (ref "U14") (pin "13") (pinfunction "VREFA_13") (pintype "bidirectional"))
    )
    (net (code "92") (name "Net-(U12B--IN)") (class "Default")
      (node (ref "R39") (pin "2") (pinfunction "2_2") (pintype "passive"))
      (node (ref "R40") (pin "2") (pinfunction "2_2") (pintype "passive"))
      (node (ref "R44") (pin "1") (pinfunction "1_1") (pintype "passive"))
      (node (ref "U12") (pin "6") (pinfunction "-IN_6") (pintype "input"))
    )
    (net (code "93") (name "Net-(U12B-OUT)") (class "Default")
      (node (ref "R44") (pin "2") (pinfunction "2_2") (pintype "passive"))
      (node (ref "U12") (pin "7") (pinfunction "OUT_7") (pintype "output"))
      (node (ref "U14") (pin "11") (pinfunction "VREFB_11") (pintype "bidirectional"))
    )
    (net (code "94") (name "Net-(U13-VOUT_A)") (class "Default")
      (node (ref "R45") (pin "1") (pinfunction "1_1") (pintype "passive"))
      (node (ref "U13") (pin "14") (pinfunction "VOUT_A_14") (pintype "bidirectional"))
    )
    (net (code "95") (name "Net-(U13-VOUT_B)") (class "Default")
      (node (ref "R46") (pin "1") (pinfunction "1_1") (pintype "passive"))
      (node (ref "U13") (pin "10") (pinfunction "VOUT_B_10") (pintype "bidirectional"))
    )
    (net (code "96") (name "Net-(U14-VOUT_A)") (class "Default")
      (node (ref "R48") (pin "1") (pinfunction "1_1") (pintype "passive"))
      (node (ref "U14") (pin "14") (pinfunction "VOUT_A_14") (pintype "bidirectional"))
    )
    (net (code "97") (name "Net-(U14-VOUT_B)") (class "Default")
      (node (ref "R49") (pin "1") (pinfunction "1_1") (pintype "passive"))
      (node (ref "U14") (pin "10") (pinfunction "VOUT_B_10") (pintype "bidirectional"))
    )
    (net (code "98") (name "Net-(U15A-+IN)") (class "Default")
      (node (ref "R51") (pin "2") (pinfunction "2_2") (pintype "passive"))
      (node (ref "R53") (pin "2") (pinfunction "2_2") (pintype "passive"))
      (node (ref "U15") (pin "3") (pinfunction "+IN_3") (pintype "input"))
    )
    (net (code "99") (name "Net-(U15A--IN)") (class "Default")
      (node (ref "R45") (pin "2") (pinfunction "2_2") (pintype "passive"))
      (node (ref "R57") (pin "1") (pinfunction "1_1") (pintype "passive"))
      (node (ref "U15") (pin "2") (pinfunction "-IN_2") (pintype "input"))
    )
    (net (code "100") (name "Net-(U15A-OUT)") (class "Default")
      (node (ref "R57") (pin "2") (pinfunction "2_2") (pintype "passive"))
      (node (ref "R61") (pin "1") (pinfunction "1_1") (pintype "passive"))
      (node (ref "U15") (pin "1") (pinfunction "OUT_1") (pintype "output"))
    )
    (net (code "101") (name "Net-(U15B-+IN)") (class "Default")
      (node (ref "R47") (pin "2") (pinfunction "2_2") (pintype "passive"))
      (node (ref "R54") (pin "2") (pinfunction "2_2") (pintype "passive"))
      (node (ref "U15") (pin "5") (pinfunction "+IN_5") (pintype "input"))
    )
    (net (code "102") (name "Net-(U15B--IN)") (class "Default")
      (node (ref "R46") (pin "2") (pinfunction "2_2") (pintype "passive"))
      (node (ref "R59") (pin "1") (pinfunction "1_1") (pintype "passive"))
      (node (ref "U15") (pin "6") (pinfunction "-IN_6") (pintype "input"))
    )
    (net (code "103") (name "Net-(U15B-OUT)") (class "Default")
      (node (ref "R59") (pin "2") (pinfunction "2_2") (pintype "passive"))
      (node (ref "R63") (pin "1") (pinfunction "1_1") (pintype "passive"))
      (node (ref "U15") (pin "7") (pinfunction "OUT_7") (pintype "output"))
    )
    (net (code "104") (name "Net-(U16A-+IN)") (class "Default")
      (node (ref "R52") (pin "2") (pinfunction "2_2") (pintype "passive"))
      (node (ref "R55") (pin "2") (pinfunction "2_2") (pintype "passive"))
      (node (ref "U16") (pin "3") (pinfunction "+IN_3") (pintype "input"))
    )
    (net (code "105") (name "Net-(U16A--IN)") (class "Default")
      (node (ref "R48") (pin "2") (pinfunction "2_2") (pintype "passive"))
      (node (ref "R58") (pin "1") (pinfunction "1_1") (pintype "passive"))
      (node (ref "U16") (pin "2") (pinfunction "-IN_2") (pintype "input"))
    )
    (net (code "106") (name "Net-(U16A-OUT)") (class "Default")
      (node (ref "R58") (pin "2") (pinfunction "2_2") (pintype "passive"))
      (node (ref "R62") (pin "1") (pinfunction "1_1") (pintype "passive"))
      (node (ref "U16") (pin "1") (pinfunction "OUT_1") (pintype "output"))
    )
    (net (code "107") (name "Net-(U16B-+IN)") (class "Default")
      (node (ref "R50") (pin "2") (pinfunction "2_2") (pintype "passive"))
      (node (ref "R56") (pin "2") (pinfunction "2_2") (pintype "passive"))
      (node (ref "U16") (pin "5") (pinfunction "+IN_5") (pintype "input"))
    )
    (net (code "108") (name "Net-(U16B--IN)") (class "Default")
      (node (ref "R49") (pin "2") (pinfunction "2_2") (pintype "passive"))
      (node (ref "R60") (pin "1") (pinfunction "1_1") (pintype "passive"))
      (node (ref "U16") (pin "6") (pinfunction "-IN_6") (pintype "input"))
    )
    (net (code "109") (name "Net-(U16B-OUT)") (class "Default")
      (node (ref "R60") (pin "2") (pinfunction "2_2") (pintype "passive"))
      (node (ref "R64") (pin "1") (pinfunction "1_1") (pintype "passive"))
      (node (ref "U16") (pin "7") (pinfunction "OUT_7") (pintype "output"))
    )
    (net (code "110") (name "Net-(U17A--IN)") (class "Default")
      (node (ref "C19") (pin "1") (pinfunction "1_1") (pintype "passive"))
      (node (ref "R65") (pin "2") (pinfunction "2_2") (pintype "passive"))
      (node (ref "R66") (pin "2") (pinfunction "2_2") (pintype "passive"))
      (node (ref "R73") (pin "1") (pinfunction "1_1") (pintype "passive"))
      (node (ref "U17") (pin "2") (pinfunction "-IN_2") (pintype "input"))
    )
    (net (code "111") (name "Net-(U17B--IN)") (class "Default")
      (node (ref "C67") (pin "1") (pinfunction "1_1") (pintype "passive"))
      (node (ref "R77") (pin "1") (pinfunction "1_1") (pintype "passive"))
      (node (ref "R81") (pin "2") (pinfunction "2_2") (pintype "passive"))
      (node (ref "R97") (pin "1") (pinfunction "1_1") (pintype "passive"))
      (node (ref "U17") (pin "6") (pinfunction "-IN_6") (pintype "input"))
    )
    (net (code "112") (name "Net-(U18A--IN)") (class "Default")
      (node (ref "C20") (pin "1") (pinfunction "1_1") (pintype "passive"))
      (node (ref "R67") (pin "2") (pinfunction "2_2") (pintype "passive"))
      (node (ref "R68") (pin "2") (pinfunction "2_2") (pintype "passive"))
      (node (ref "R74") (pin "1") (pinfunction "1_1") (pintype "passive"))
      (node (ref "U18") (pin "2") (pinfunction "-IN_2") (pintype "input"))
    )
    (net (code "113") (name "Net-(U18B--IN)") (class "Default")
      (node (ref "C68") (pin "1") (pinfunction "1_1") (pintype "passive"))
      (node (ref "R78") (pin "1") (pinfunction "1_1") (pintype "passive"))
      (node (ref "R82") (pin "2") (pinfunction "2_2") (pintype "passive"))
      (node (ref "R98") (pin "1") (pinfunction "1_1") (pintype "passive"))
      (node (ref "U18") (pin "6") (pinfunction "-IN_6") (pintype "input"))
    )
    (net (code "114") (name "Net-(U19A--IN)") (class "Default")
      (node (ref "C21") (pin "1") (pinfunction "1_1") (pintype "passive"))
      (node (ref "R69") (pin "2") (pinfunction "2_2") (pintype "passive"))
      (node (ref "R70") (pin "2") (pinfunction "2_2") (pintype "passive"))
      (node (ref "R75") (pin "1") (pinfunction "1_1") (pintype "passive"))
      (node (ref "U19") (pin "2") (pinfunction "-IN_2") (pintype "input"))
    )
    (net (code "115") (name "Net-(U19B--IN)") (class "Default")
      (node (ref "C69") (pin "1") (pinfunction "1_1") (pintype "passive"))
      (node (ref "R79") (pin "1") (pinfunction "1_1") (pintype "passive"))
      (node (ref "R83") (pin "2") (pinfunction "2_2") (pintype "passive"))
      (node (ref "R99") (pin "1") (pinfunction "1_1") (pintype "passive"))
      (node (ref "U19") (pin "6") (pinfunction "-IN_6") (pintype "input"))
    )
    (net (code "116") (name "Net-(U20A--IN)") (class "Default")
      (node (ref "C22") (pin "1") (pinfunction "1_1") (pintype "passive"))
      (node (ref "R71") (pin "2") (pinfunction "2_2") (pintype "passive"))
      (node (ref "R72") (pin "2") (pinfunction "2_2") (pintype "passive"))
      (node (ref "R76") (pin "1") (pinfunction "1_1") (pintype "passive"))
      (node (ref "U20") (pin "2") (pinfunction "-IN_2") (pintype "input"))
    )
    (net (code "117") (name "Net-(U20B--IN)") (class "Default")
      (node (ref "C70") (pin "1") (pinfunction "1_1") (pintype "passive"))
      (node (ref "R100") (pin "1") (pinfunction "1_1") (pintype "passive"))
      (node (ref "R101") (pin "2") (pinfunction "2_2") (pintype "passive"))
      (node (ref "R80") (pin "1") (pinfunction "1_1") (pintype "passive"))
      (node (ref "U20") (pin "6") (pinfunction "-IN_6") (pintype "input"))
    )
    (net (code "118") (name "Net-(U21-PF0{slash}OSC_IN)") (class "Default")
      (node (ref "C26") (pin "2") (pinfunction "2_2") (pintype "passive"))
      (node (ref "U21") (pin "5") (pinfunction "PF0/OSC_IN_5") (pintype "bidirectional"))
      (node (ref "X1") (pin "P$2") (pinfunction "P$2_P$2") (pintype "bidirectional"))
    )
    (net (code "119") (name "Net-(U21-PF1{slash}OSC_OUT)") (class "Default")
      (node (ref "C27") (pin "2") (pinfunction "2_2") (pintype "passive"))
      (node (ref "U21") (pin "6") (pinfunction "PF1/OSC_OUT_6") (pintype "bidirectional"))
      (node (ref "X1") (pin "P$1") (pinfunction "P$1_P$1") (pintype "bidirectional"))
    )
    (net (code "120") (name "OUT_L") (class "Default")
      (node (ref "C32") (pin "2") (pinfunction "2_2") (pintype "passive"))
      (node (ref "C65") (pin "+") (pinfunction "+_+") (pintype "passive"))
      (node (ref "R88") (pin "2") (pinfunction "2_2") (pintype "passive"))
      (node (ref "U22") (pin "1") (pinfunction "OUT_1") (pintype "output"))
    )
    (net (code "121") (name "OUT_R") (class "Default")
      (node (ref "C33") (pin "2") (pinfunction "2_2") (pintype "passive"))
      (node (ref "C66") (pin "+") (pinfunction "+_+") (pintype "passive"))
      (node (ref "R89") (pin "2") (pinfunction "2_2") (pintype "passive"))
      (node (ref "U22") (pin "7") (pinfunction "OUT_7") (pintype "output"))
    )
    (net (code "122") (name "PAN_1_POT") (class "Default")
      (node (ref "C61") (pin "1") (pinfunction "1_1") (pintype "passive"))
      (node (ref "IC1") (pin "1") (pinfunction "X4_1") (pintype "bidirectional"))
      (node (ref "VR3") (pin "2") (pinfunction "S_2") (pintype "passive"))
    )
    (net (code "123") (name "PAN_2_POT") (class "Default")
      (node (ref "C62") (pin "1") (pinfunction "1_1") (pintype "passive"))
      (node (ref "IC1") (pin "5") (pinfunction "X5_5") (pintype "bidirectional"))
      (node (ref "VR7") (pin "2") (pinfunction "S_2") (pintype "passive"))
    )
    (net (code "124") (name "PAN_3_POT") (class "Default")
      (node (ref "C63") (pin "1") (pinfunction "1_1") (pintype "passive"))
      (node (ref "IC1") (pin "2") (pinfunction "X6_2") (pintype "bidirectional"))
      (node (ref "VR4") (pin "2") (pinfunction "S_2") (pintype "passive"))
    )
    (net (code "125") (name "PAN_4_POT") (class "Default")
      (node (ref "C64") (pin "1") (pinfunction "1_1") (pintype "passive"))
      (node (ref "IC1") (pin "4") (pinfunction "X7_4") (pintype "bidirectional"))
      (node (ref "VR8") (pin "2") (pinfunction "S_2") (pintype "passive"))
    )
    (net (code "126") (name "PAN_CV_1") (class "Default")
      (node (ref "C19") (pin "2") (pinfunction "2_2") (pintype "passive"))
      (node (ref "R73") (pin "2") (pinfunction "2_2") (pintype "passive"))
      (node (ref "U17") (pin "1") (pinfunction "OUT_1") (pintype "output"))
      (node (ref "U21") (pin "14") (pinfunction "PA4/SPI1_NSS/USART2_CK/TIM14_CH1/ADC_IN4_14") (pintype "bidirectional"))
    )
    (net (code "127") (name "PAN_CV_2") (class "Default")
      (node (ref "C20") (pin "2") (pinfunction "2_2") (pintype "passive"))
      (node (ref "R74") (pin "2") (pinfunction "2_2") (pintype "passive"))
      (node (ref "U18") (pin "1") (pinfunction "OUT_1") (pintype "output"))
      (node (ref "U21") (pin "15") (pinfunction "PA5/SPI1_SCK/ADC_IN5_15") (pintype "bidirectional"))
    )
    (net (code "128") (name "PAN_CV_3") (class "Default")
      (node (ref "C21") (pin "2") (pinfunction "2_2") (pintype "passive"))
      (node (ref "R75") (pin "2") (pinfunction "2_2") (pintype "passive"))
      (node (ref "U19") (pin "1") (pinfunction "OUT_1") (pintype "output"))
      (node (ref "U21") (pin "16") (pinfunction "PA6/SPI1_MISO/TIM3_CH1/TIM1_BKIN/TIM16_CH1/EVENTOUT/ADC_IN6_16") (pintype "bidirectional"))
    )
    (net (code "129") (name "PAN_CV_4") (class "Default")
      (node (ref "C22") (pin "2") (pinfunction "2_2") (pintype "passive"))
      (node (ref "R76") (pin "2") (pinfunction "2_2") (pintype "passive"))
      (node (ref "U20") (pin "1") (pinfunction "OUT_1") (pintype "output"))
      (node (ref "U21") (pin "17") (pinfunction "PA7/SPI1_MOSI/TIM3_CH2/TIM14_CH1/TIM1_CH1N/TIM17_CH1/EVENTOUT/ADC_IN7_17") (pintype "bidirectional"))
    )
    (net (code "130") (name "POT_MUX") (class "Default")
      (node (ref "IC1") (pin "3") (pinfunction "X_3") (pintype "bidirectional"))
      (node (ref "U21") (pin "18") (pinfunction "PB0/TIM3_CH3/TIM1_CH2N/EVENTOUT/ADC_IN8_18") (pintype "bidirectional"))
    )
    (net (code "131") (name "SCK") (class "Default")
      (node (ref "U1") (pin "3") (pinfunction "SCK_3") (pintype "input"))
      (node (ref "U10") (pin "3") (pinfunction "SCK_3") (pintype "input"))
      (node (ref "U13") (pin "4") (pinfunction "SCK_4") (pintype "bidirectional"))
      (node (ref "U14") (pin "4") (pinfunction "SCK_4") (pintype "bidirectional"))
      (node (ref "U2") (pin "3") (pinfunction "SCK_3") (pintype "input"))
      (node (ref "U21") (pin "39") (pinfunction "PB3/SPI1_SCK/EVENTOUT_39") (pintype "bidirectional"))
      (node (ref "U5") (pin "4") (pinfunction "SCK_4") (pintype "bidirectional"))
      (node (ref "U6") (pin "4") (pinfunction "SCK_4") (pintype "bidirectional"))
      (node (ref "U9") (pin "3") (pinfunction "SCK_3") (pintype "input"))
    )
    (net (code "132") (name "SUM_L") (class "Default")
      (node (ref "C32") (pin "1") (pinfunction "1_1") (pintype "passive"))
      (node (ref "R29") (pin "2") (pinfunction "2_2") (pintype "passive"))
      (node (ref "R31") (pin "2") (pinfunction "2_2") (pintype "passive"))
      (node (ref "R61") (pin "2") (pinfunction "2_2") (pintype "passive"))
      (node (ref "R62") (pin "2") (pinfunction "2_2") (pintype "passive"))
      (node (ref "R88") (pin "1") (pinfunction "1_1") (pintype "passive"))
      (node (ref "U22") (pin "2") (pinfunction "-IN_2") (pintype "input"))
    )
    (net (code "133") (name "SUM_R") (class "Default")
      (node (ref "C33") (pin "1") (pinfunction "1_1") (pintype "passive"))
      (node (ref "R30") (pin "2") (pinfunction "2_2") (pintype "passive"))
      (node (ref "R32") (pin "2") (pinfunction "2_2") (pintype "passive"))
      (node (ref "R63") (pin "2") (pinfunction "2_2") (pintype "passive"))
      (node (ref "R64") (pin "2") (pinfunction "2_2") (pintype "passive"))
      (node (ref "R89") (pin "1") (pinfunction "1_1") (pintype "passive"))
      (node (ref "U22") (pin "6") (pinfunction "-IN_6") (pintype "input"))
    )
    (net (code "134") (name "SWDCLK") (class "Default")
      (node (ref "J17") (pin "4") (pinfunction "SWDCLK/TCK_4") (pintype "bidirectional"))
      (node (ref "U21") (pin "37") (pinfunction "PA14/USART2_TX/SWCLK_37") (pintype "bidirectional"))
    )
    (net (code "135") (name "SWDIO") (class "Default")
      (node (ref "J17") (pin "2") (pinfunction "SWDIO/TMS_2") (pintype "bidirectional"))
      (node (ref "U21") (pin "34") (pinfunction "PA13/IR_OUT/SWDIO_34") (pintype "bidirectional"))
    )
    (net (code "136") (name "SWITCH_1") (class "Default")
      (node (ref "S1") (pin "1") (pinfunction "1_1") (pintype "passive"))
      (node (ref "S1") (pin "2") (pinfunction "2_2") (pintype "passive"))
      (node (ref "U21") (pin "33") (pinfunction "PA12/USART1_RTS/TIM1_ETR/EVENTOUT_33") (pintype "bidirectional"))
    )
    (net (code "137") (name "SWITCH_2") (class "Default")
      (node (ref "S2") (pin "1") (pinfunction "1_1") (pintype "passive"))
      (node (ref "S2") (pin "2") (pinfunction "2_2") (pintype "passive"))
      (node (ref "U21") (pin "19") (pinfunction "PB1/TIM3_CH4/TIM14_CH1/TIM1_CH3N/ADC_IN9_19") (pintype "bidirectional"))
    )
    (net (code "138") (name "SWITCH_3") (class "Default")
      (node (ref "S3") (pin "1") (pinfunction "1_1") (pintype "passive"))
      (node (ref "S3") (pin "2") (pinfunction "2_2") (pintype "passive"))
      (node (ref "U21") (pin "20") (pinfunction "PB2_20") (pintype "bidirectional"))
    )
    (net (code "139") (name "SWITCH_4") (class "Default")
      (node (ref "S4") (pin "3") (pinfunction "3_3") (pintype "passive"))
      (node (ref "S4") (pin "4") (pinfunction "4_4") (pintype "passive"))
      (node (ref "U21") (pin "42") (pinfunction "PB6/I2C1_SCL/USART1_TX/TIM16_CH1N_42") (pintype "bidirectional"))
    )
    (net (code "140") (name "VOL_1_POT") (class "Default")
      (node (ref "C57") (pin "1") (pinfunction "1_1") (pintype "passive"))
      (node (ref "IC1") (pin "13") (pinfunction "X0_13") (pintype "bidirectional"))
      (node (ref "VR1") (pin "2") (pinfunction "S_2") (pintype "passive"))
    )
    (net (code "141") (name "VOL_2_POT") (class "Default")
      (node (ref "C58") (pin "1") (pinfunction "1_1") (pintype "passive"))
      (node (ref "IC1") (pin "14") (pinfunction "X1_14") (pintype "bidirectional"))
      (node (ref "VR5") (pin "2") (pinfunction "S_2") (pintype "passive"))
    )
    (net (code "142") (name "VOL_3_POT") (class "Default")
      (node (ref "C59") (pin "1") (pinfunction "1_1") (pintype "passive"))
      (node (ref "IC1") (pin "15") (pinfunction "X2_15") (pintype "bidirectional"))
      (node (ref "VR2") (pin "2") (pinfunction "S_2") (pintype "passive"))
    )
    (net (code "143") (name "VOL_4_POT") (class "Default")
      (node (ref "C60") (pin "1") (pinfunction "1_1") (pintype "passive"))
      (node (ref "IC1") (pin "12") (pinfunction "X3_12") (pintype "bidirectional"))
      (node (ref "VR6") (pin "2") (pinfunction "S_2") (pintype "passive"))
    )
    (net (code "144") (name "VOL_CV_1") (class "Default")
      (node (ref "C67") (pin "2") (pinfunction "2_2") (pintype "passive"))
      (node (ref "R97") (pin "2") (pinfunction "2_2") (pintype "passive"))
      (node (ref "U17") (pin "7") (pinfunction "OUT_7") (pintype "output"))
      (node (ref "U21") (pin "10") (pinfunction "PA0/USART2_CTS/ADC_IN0/RTC_TAMP2/WKUP1_10") (pintype "bidirectional"))
    )
    (net (code "145") (name "VOL_CV_2") (class "Default")
      (node (ref "C68") (pin "2") (pinfunction "2_2") (pintype "passive"))
      (node (ref "R98") (pin "2") (pinfunction "2_2") (pintype "passive"))
      (node (ref "U18") (pin "7") (pinfunction "OUT_7") (pintype "output"))
      (node (ref "U21") (pin "11") (pinfunction "PA1/USART2_RTS/EVENTOUT/ADC_IN1_11") (pintype "bidirectional"))
    )
    (net (code "146") (name "VOL_CV_3") (class "Default")
      (node (ref "C69") (pin "2") (pinfunction "2_2") (pintype "passive"))
      (node (ref "R99") (pin "2") (pinfunction "2_2") (pintype "passive"))
      (node (ref "U19") (pin "7") (pinfunction "OUT_7") (pintype "output"))
      (node (ref "U21") (pin "12") (pinfunction "PA2/USART2_TX/TIM15_CH1/ADC_IN2_12") (pintype "bidirectional"))
    )
    (net (code "147") (name "VOL_CV_4") (class "Default")
      (node (ref "C70") (pin "2") (pinfunction "2_2") (pintype "passive"))
      (node (ref "R100") (pin "2") (pinfunction "2_2") (pintype "passive"))
      (node (ref "U20") (pin "7") (pinfunction "OUT_7") (pintype "output"))
      (node (ref "U21") (pin "13") (pinfunction "PA3/USART2_RX/TIM15_CH2/ADC_IN3_13") (pintype "bidirectional"))
    )
    (net (code "148") (name "unconnected-(J1-3-PadP$2_SWITCH)") (class "Default")
      (node (ref "J1") (pin "P$2_SWITCH") (pinfunction "3_P$2_SWITCH") (pintype "passive"))
    )
    (net (code "149") (name "unconnected-(J3-3-PadP$2_SWITCH)") (class "Default")
      (node (ref "J3") (pin "P$2_SWITCH") (pinfunction "3_P$2_SWITCH") (pintype "passive"))
    )
    (net (code "150") (name "unconnected-(J5-3-PadP$2_SWITCH)") (class "Default")
      (node (ref "J5") (pin "P$2_SWITCH") (pinfunction "3_P$2_SWITCH") (pintype "passive"))
    )
    (net (code "151") (name "unconnected-(J7-3-PadP$2_SWITCH)") (class "Default")
      (node (ref "J7") (pin "P$2_SWITCH") (pinfunction "3_P$2_SWITCH") (pintype "passive"))
    )
    (net (code "152") (name "unconnected-(J9-3-PadP$2_SWITCH)") (class "Default")
      (node (ref "J9") (pin "P$2_SWITCH") (pinfunction "3_P$2_SWITCH") (pintype "passive"))
    )
    (net (code "153") (name "unconnected-(J10-3-PadP$2_SWITCH)") (class "Default")
      (node (ref "J10") (pin "P$2_SWITCH") (pinfunction "3_P$2_SWITCH") (pintype "passive"))
    )
    (net (code "154") (name "unconnected-(J11-3-PadP$2_SWITCH)") (class "Default")
      (node (ref "J11") (pin "P$2_SWITCH") (pinfunction "3_P$2_SWITCH") (pintype "passive"))
    )
    (net (code "155") (name "unconnected-(J12-3-PadP$2_SWITCH)") (class "Default")
      (node (ref "J12") (pin "P$2_SWITCH") (pinfunction "3_P$2_SWITCH") (pintype "passive"))
    )
    (net (code "156") (name "unconnected-(J13-3-PadP$2_SWITCH)") (class "Default")
      (node (ref "J13") (pin "P$2_SWITCH") (pinfunction "3_P$2_SWITCH") (pintype "passive"))
    )
    (net (code "157") (name "unconnected-(J14-3-PadP$2_SWITCH)") (class "Default")
      (node (ref "J14") (pin "P$2_SWITCH") (pinfunction "3_P$2_SWITCH") (pintype "passive"))
    )
    (net (code "158") (name "unconnected-(J15-3-PadP$2_SWITCH)") (class "Default")
      (node (ref "J15") (pin "P$2_SWITCH") (pinfunction "3_P$2_SWITCH") (pintype "passive"))
    )
    (net (code "159") (name "unconnected-(J16-3-PadP$2_SWITCH)") (class "Default")
      (node (ref "J16") (pin "P$2_SWITCH") (pinfunction "3_P$2_SWITCH") (pintype "passive"))
    )
    (net (code "160") (name "unconnected-(J17-KEY-Pad7)") (class "Default")
      (node (ref "J17") (pin "7") (pinfunction "KEY_7") (pintype "bidirectional"))
    )
    (net (code "161") (name "unconnected-(J17-NC{slash}TDI-Pad8)") (class "Default")
      (node (ref "J17") (pin "8") (pinfunction "NC/TDI_8") (pintype "bidirectional"))
    )
    (net (code "162") (name "unconnected-(J17-SWO{slash}TDO-Pad6)") (class "Default")
      (node (ref "J17") (pin "6") (pinfunction "SWO/TDO_6") (pintype "bidirectional"))
    )
    (net (code "163") (name "unconnected-(J19-3-PadP$2_SWITCH)") (class "Default")
      (node (ref "J19") (pin "P$2_SWITCH") (pinfunction "3_P$2_SWITCH") (pintype "passive"))
    )
  )
)
